# canSlaveV06a.net
KiCad netlist of a schematic drawn in EAGLE
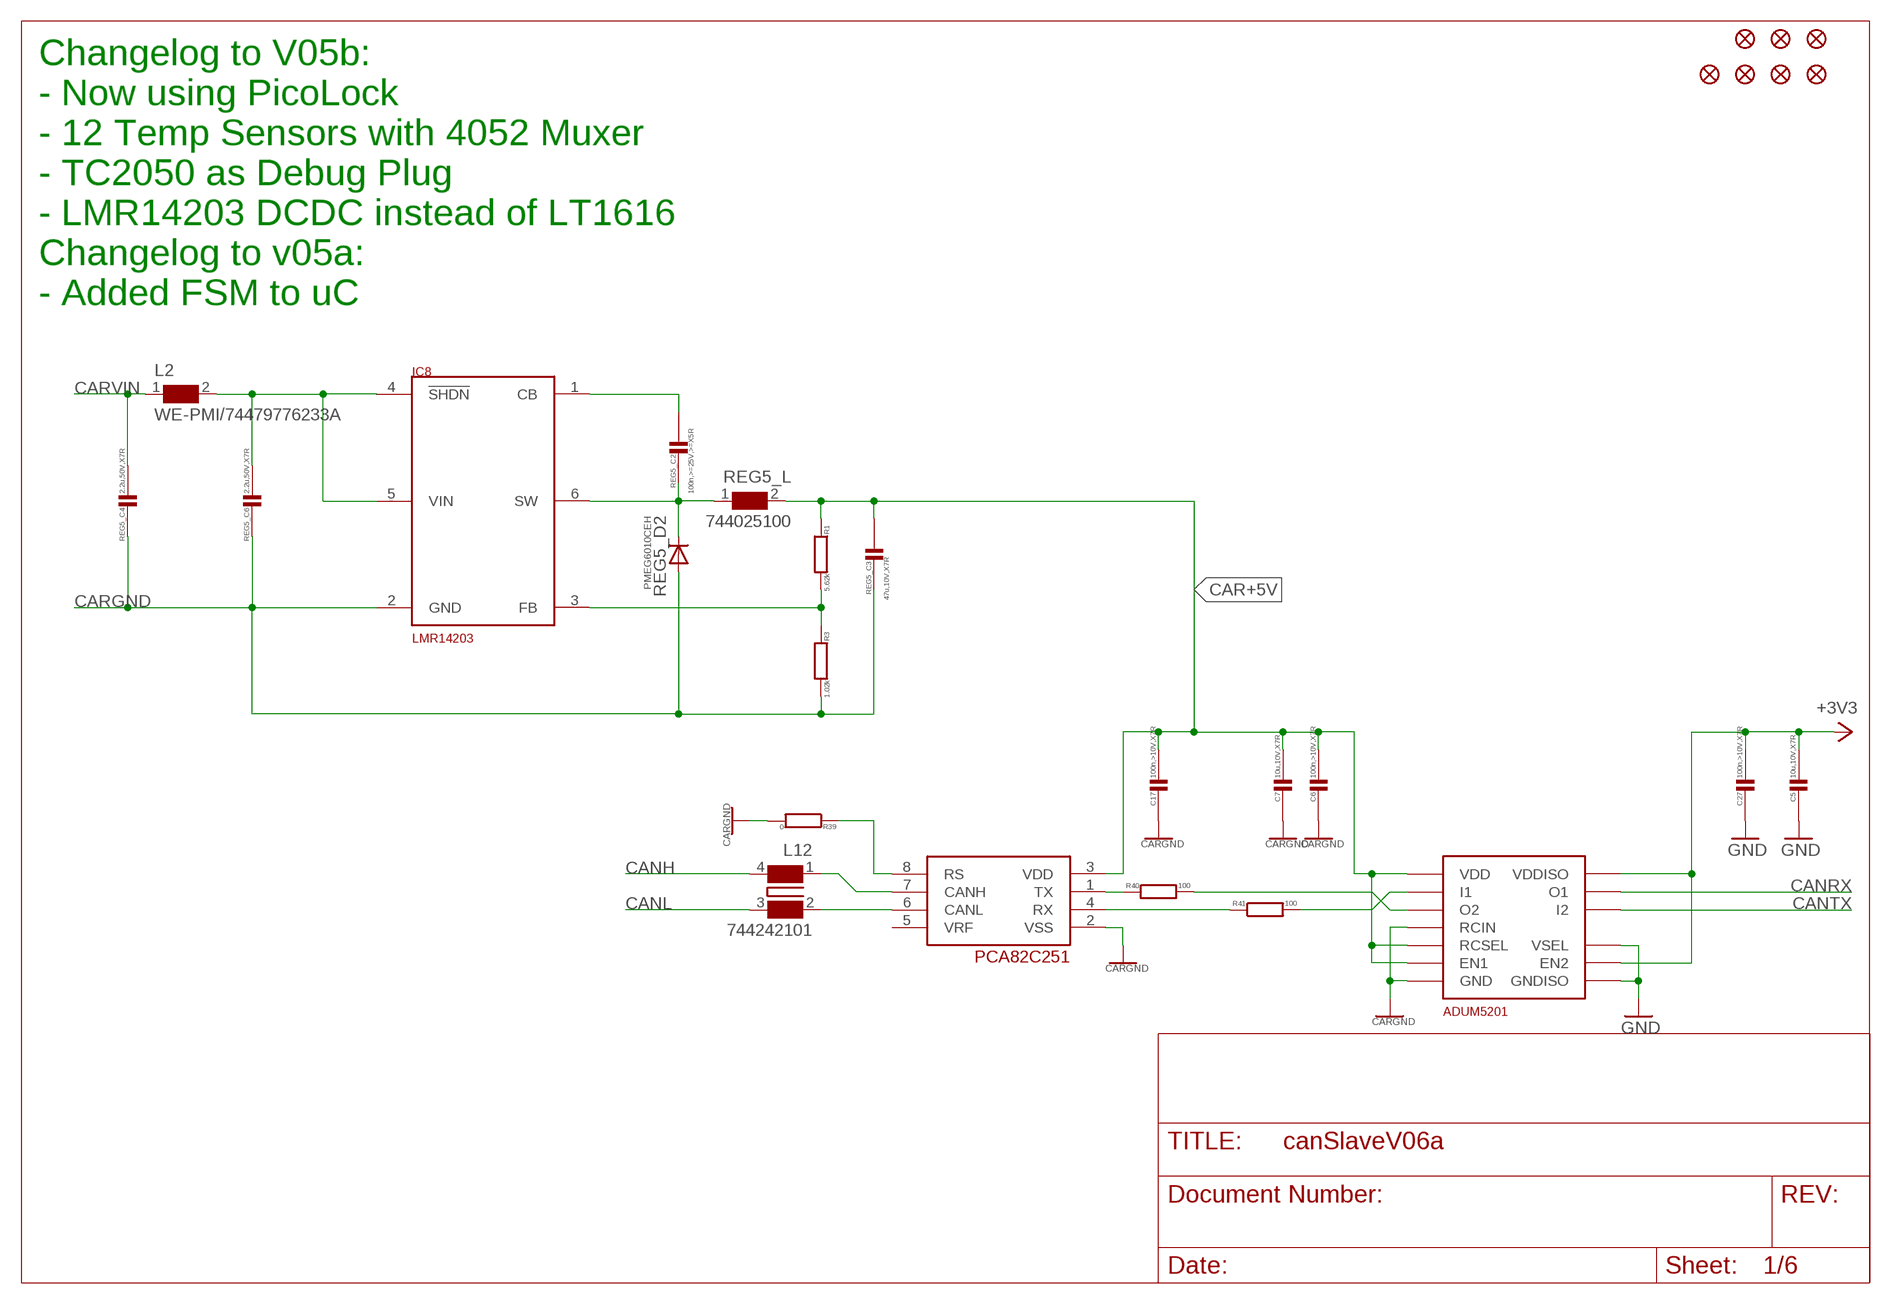
[diagram p0: schematic, sheet 1]
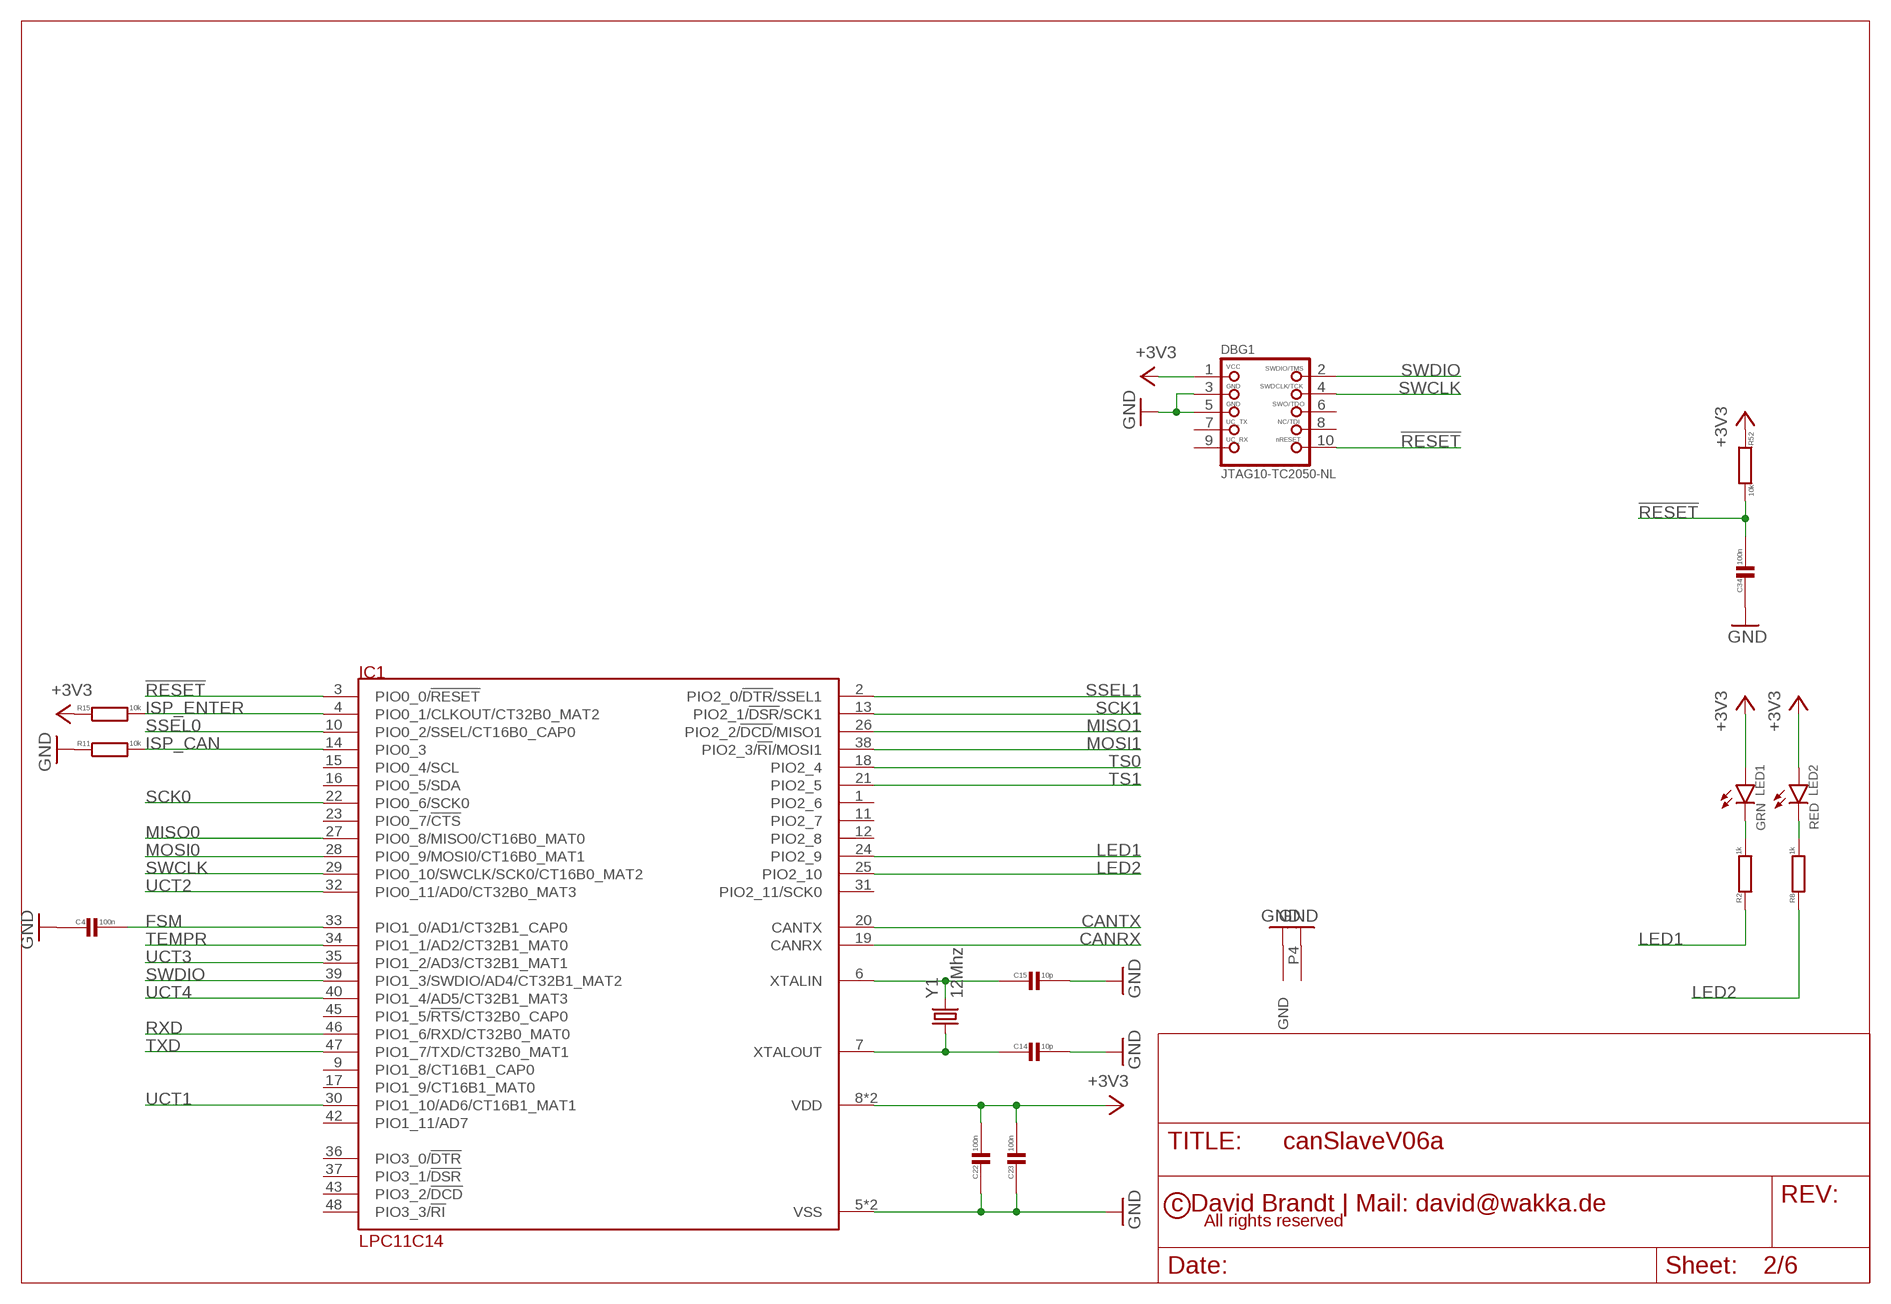
[diagram p1: schematic, sheet 2]
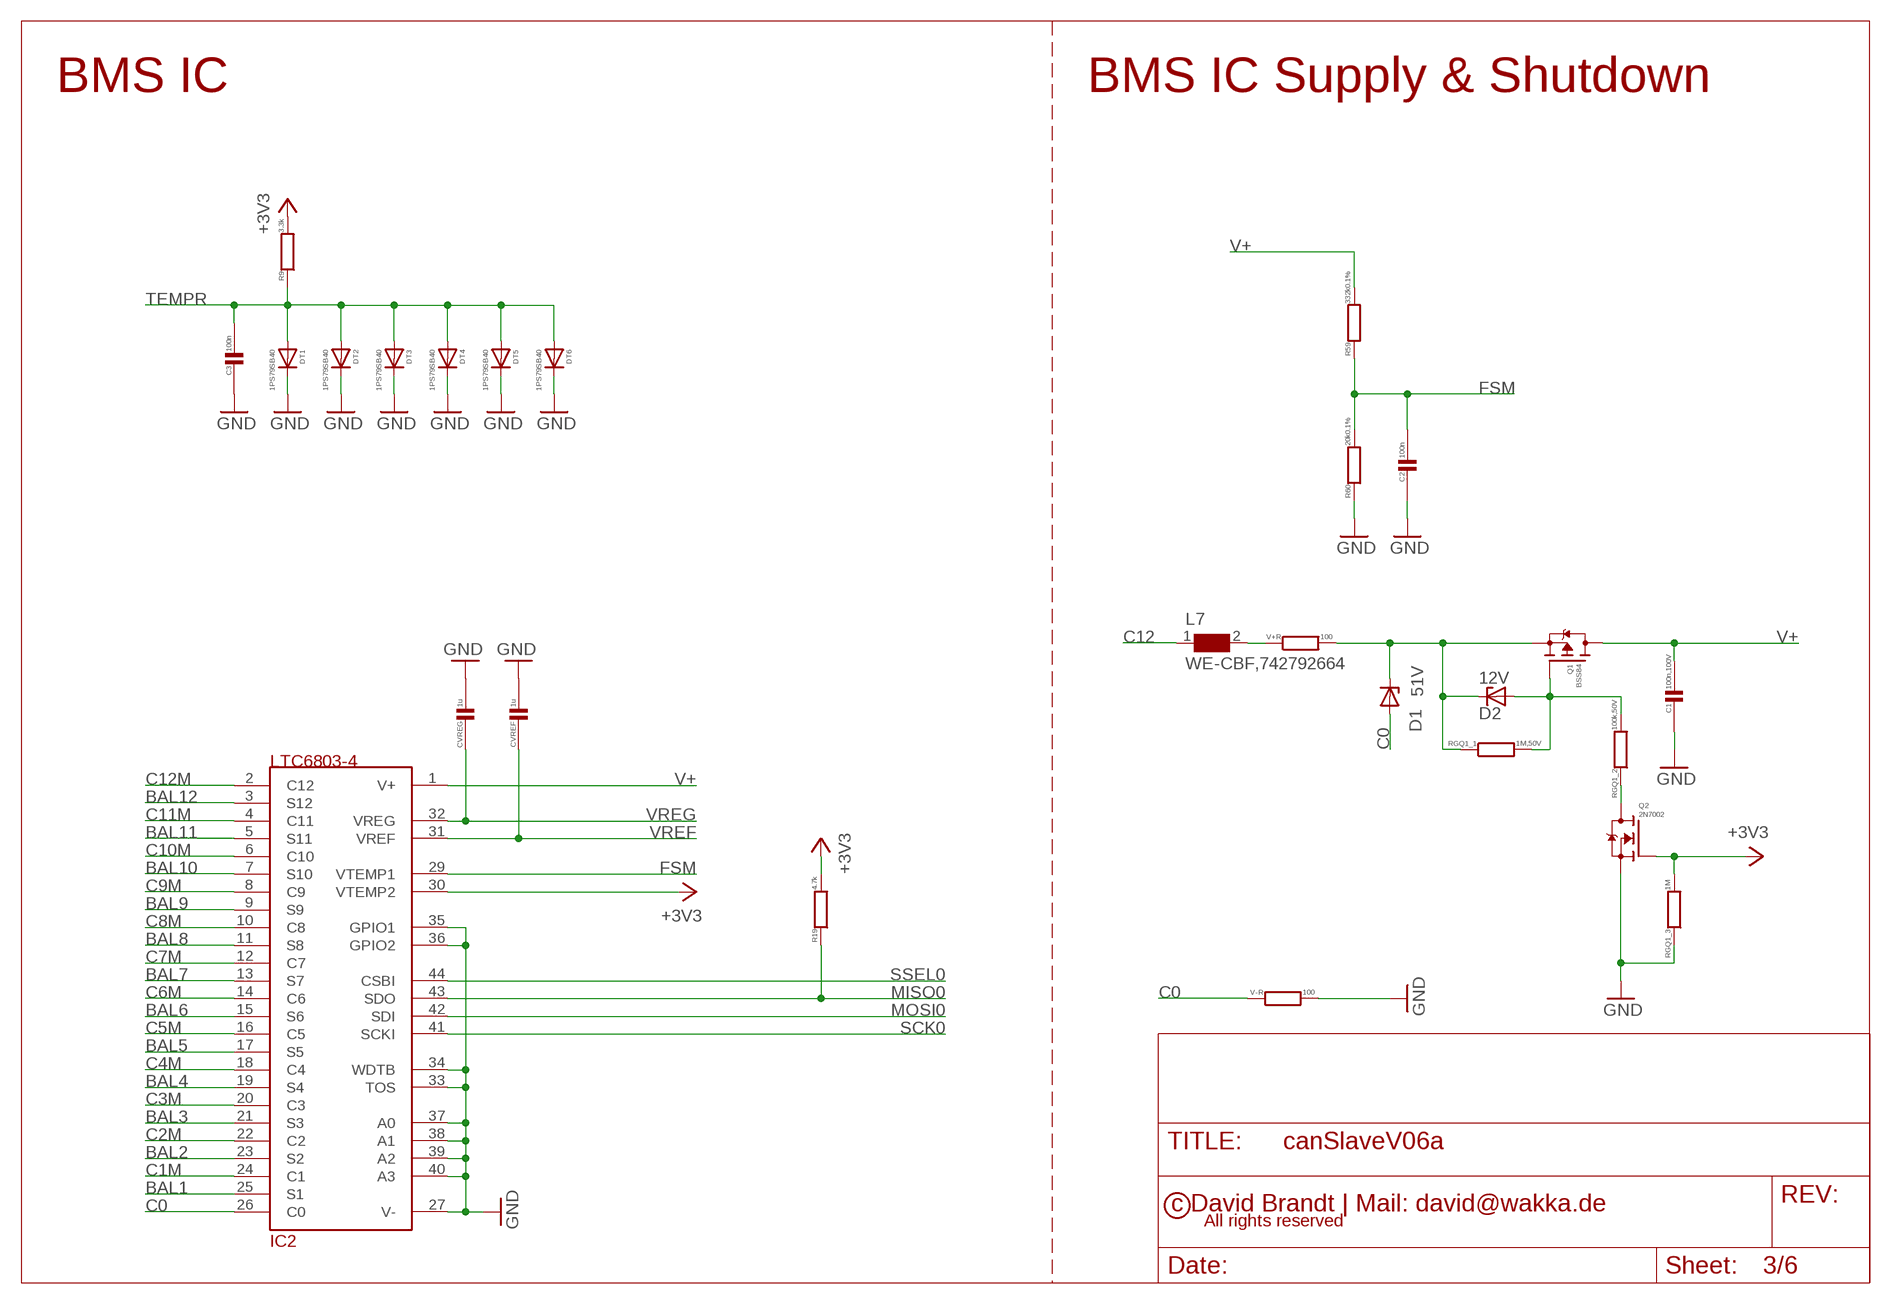
[diagram p2: schematic, sheet 3]
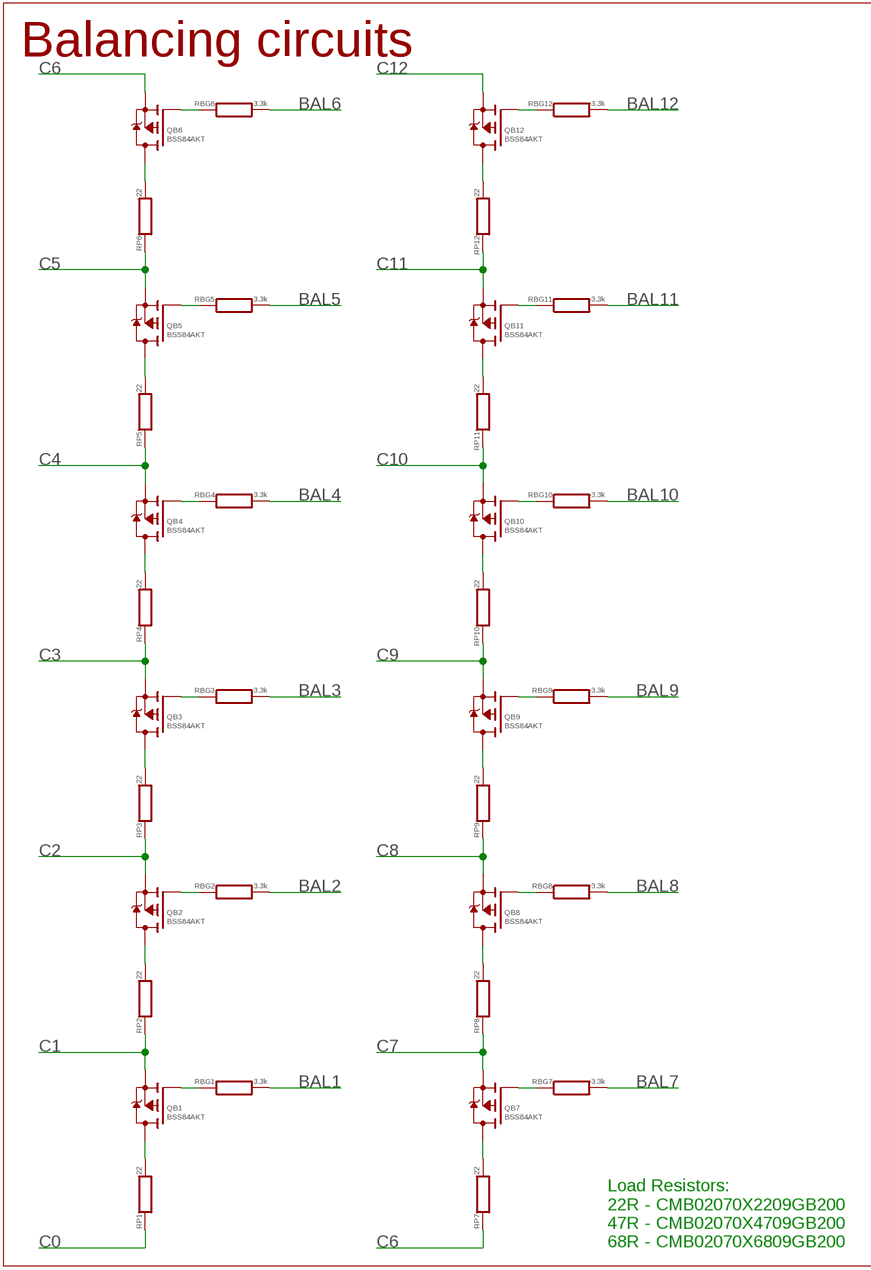
[diagram p3: schematic, sheet 4, part 1 of 2]
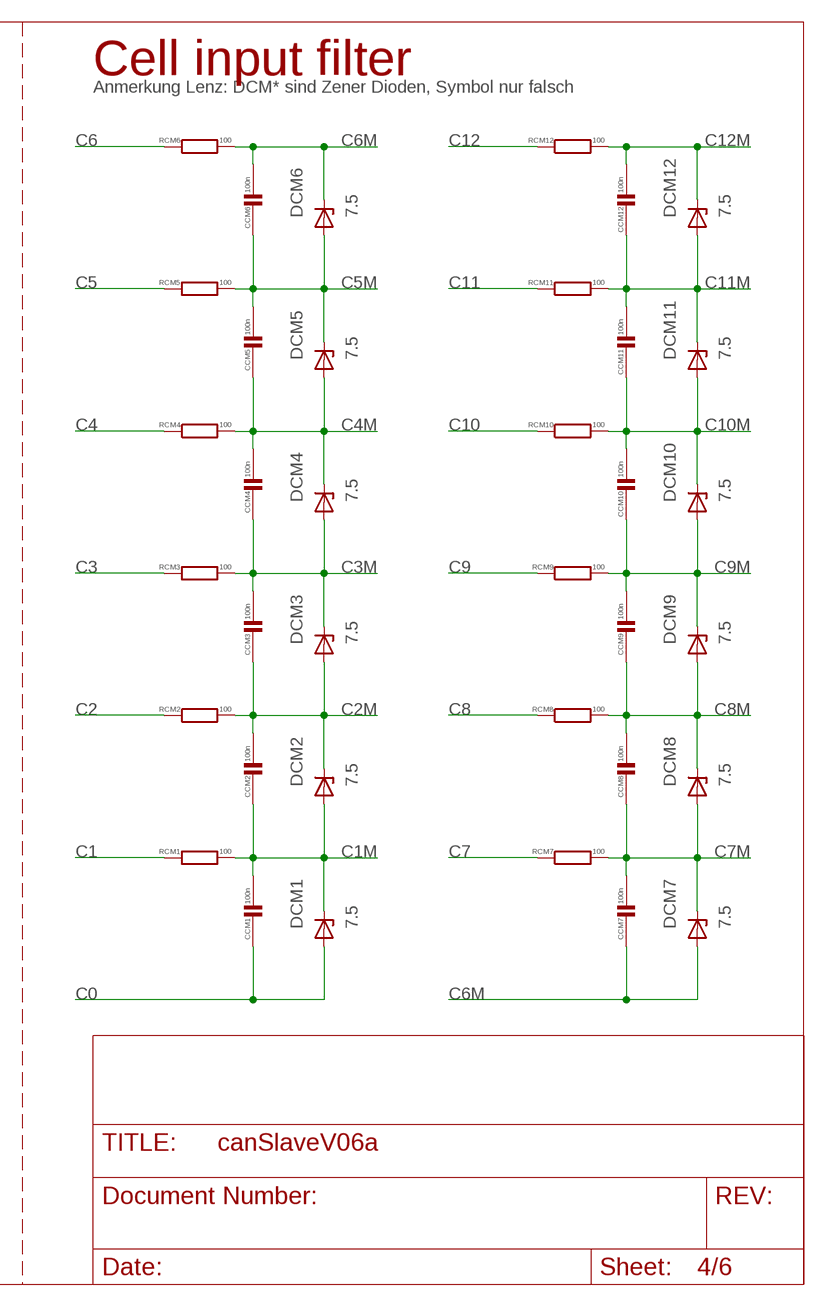
[diagram p4: schematic, sheet 4, part 2 of 2]
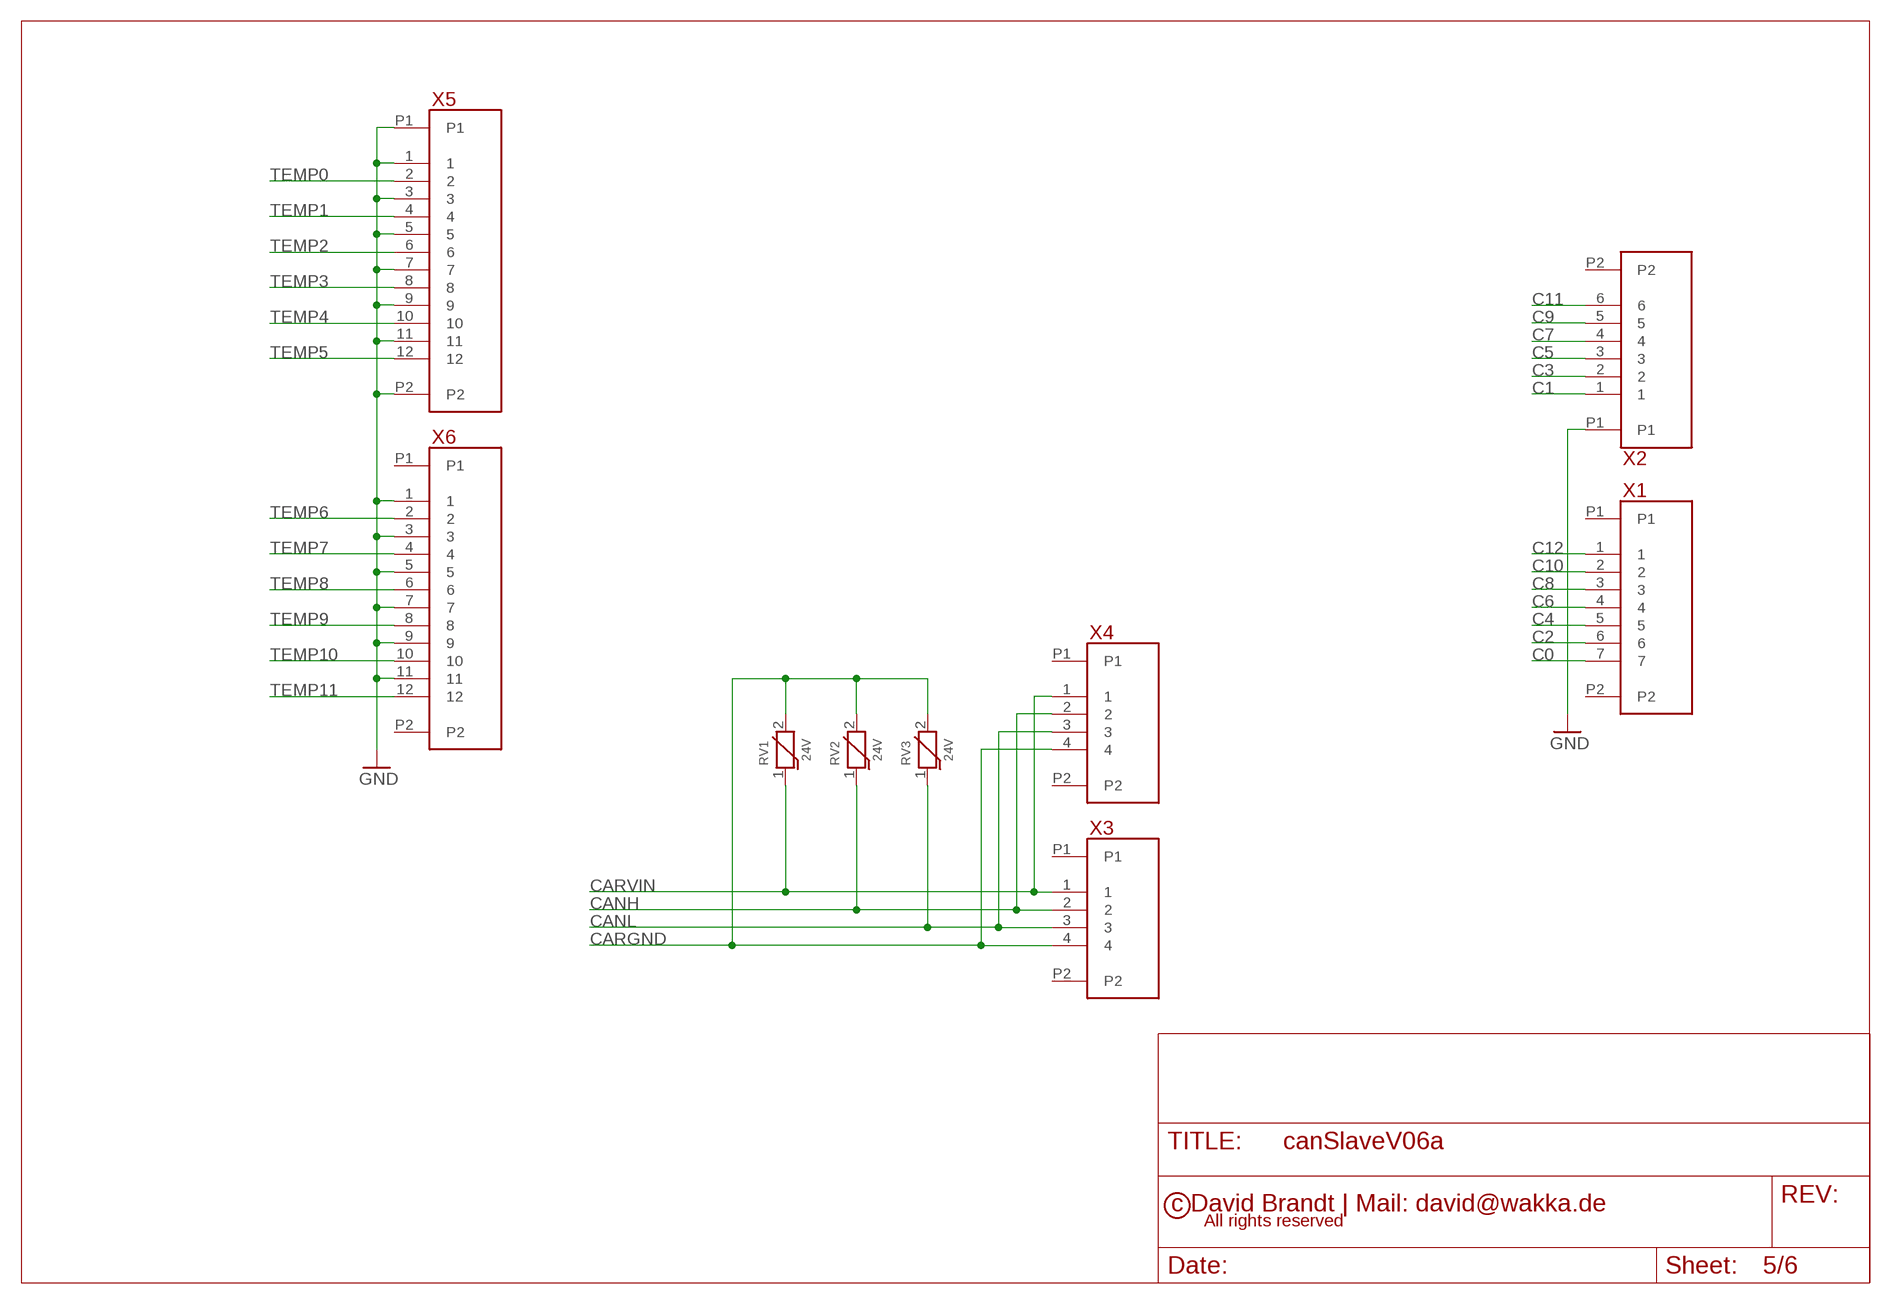
[diagram p5: schematic, sheet 5]
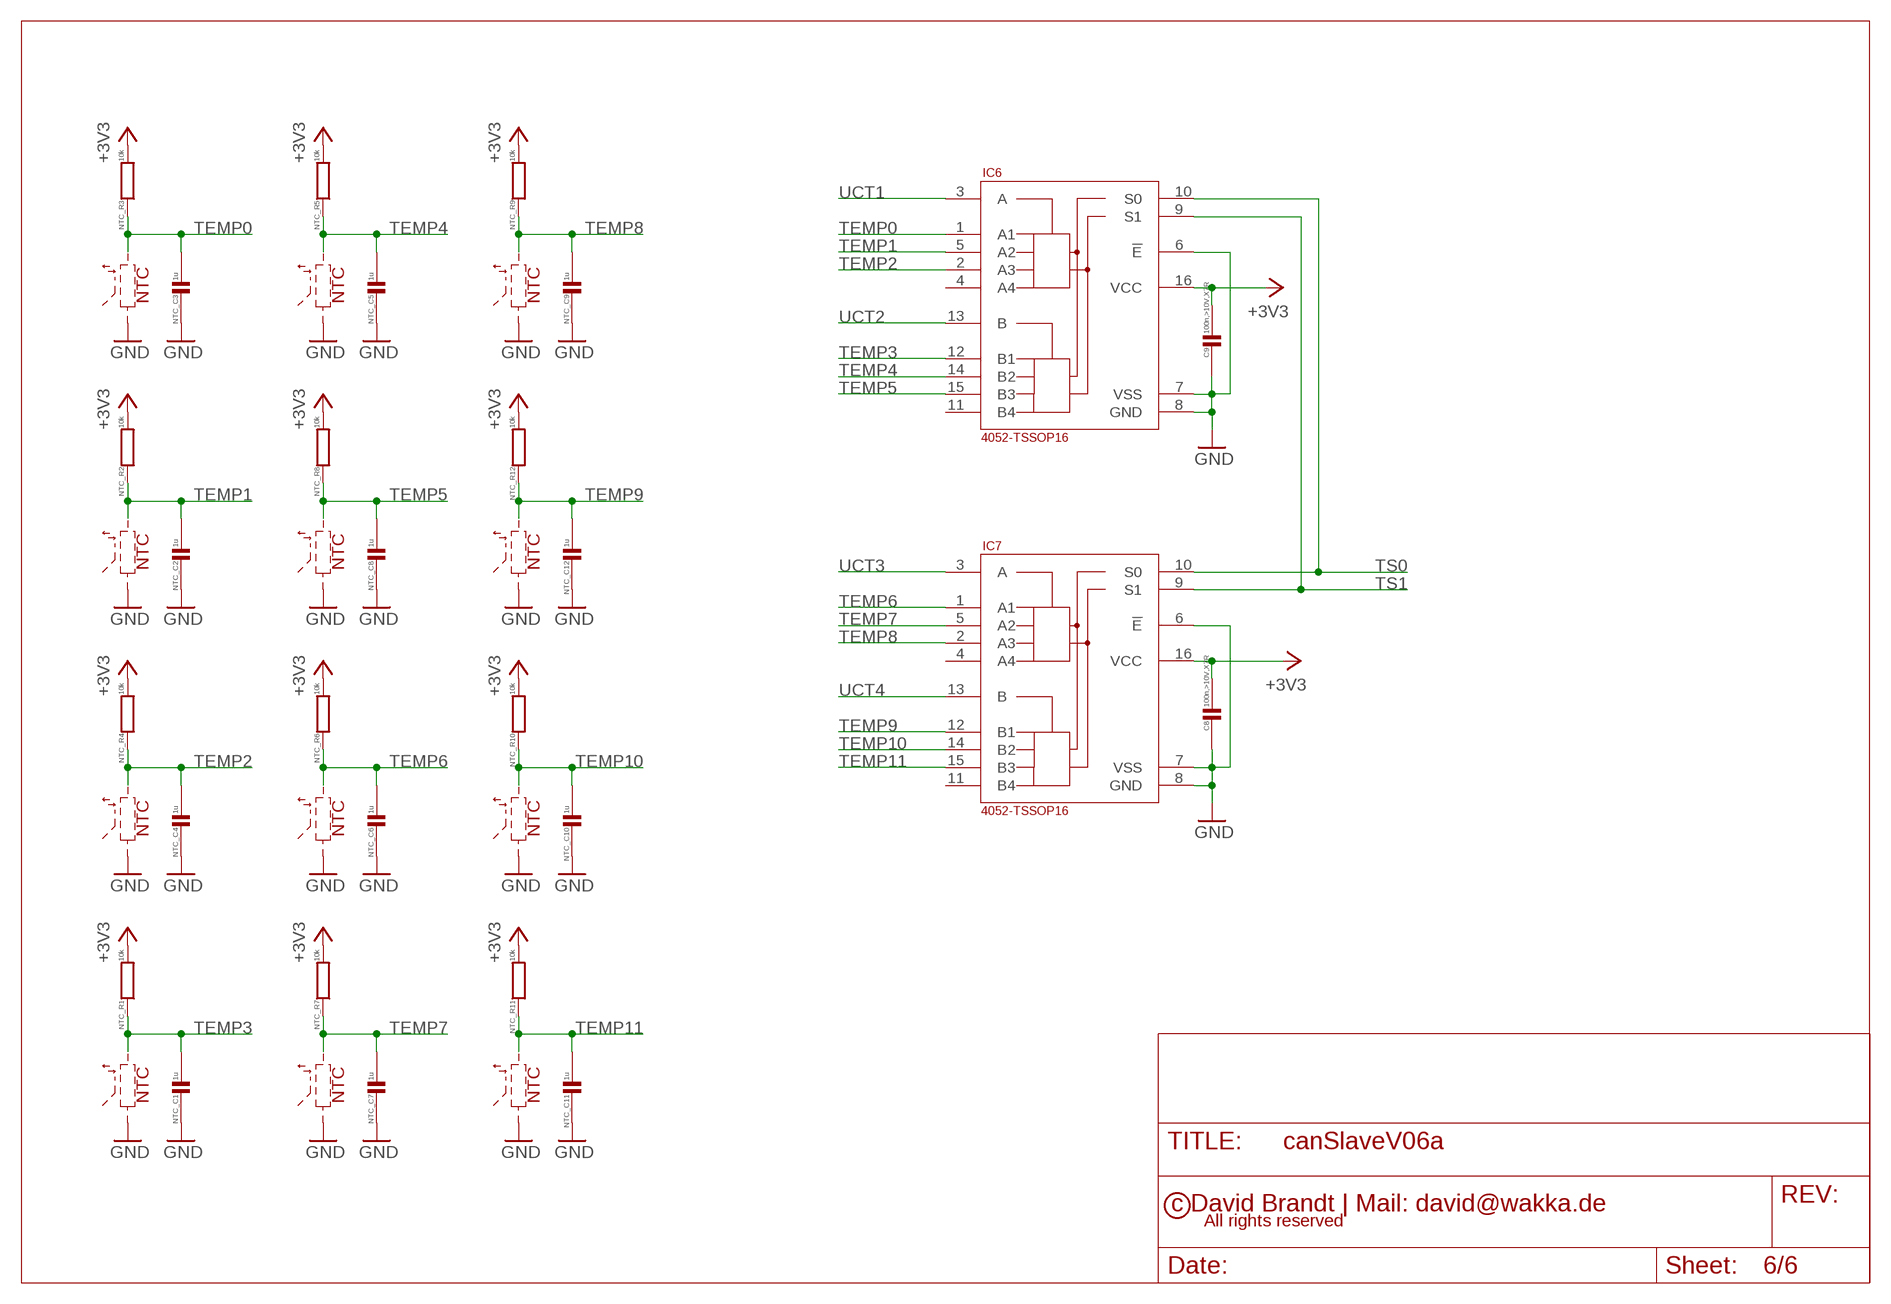
[diagram p6: schematic, sheet 6]

(export (version "E")
  (design (tool "Eeschema 10.0.6"))
  (components
    (comp (ref "CCM1")
      (value "100n")
      (footprint "eagle-import:C0402")
      (libsource (lib "eagle-import") (part "C0402"))
    )
    (comp (ref "CCM2")
      (value "100n")
      (footprint "eagle-import:C0402")
      (libsource (lib "eagle-import") (part "C0402"))
    )
    (comp (ref "CCM3")
      (value "100n")
      (footprint "eagle-import:C0402")
      (libsource (lib "eagle-import") (part "C0402"))
    )
    (comp (ref "CCM4")
      (value "100n")
      (footprint "eagle-import:C0402")
      (libsource (lib "eagle-import") (part "C0402"))
    )
    (comp (ref "CCM5")
      (value "100n")
      (footprint "eagle-import:C0402")
      (libsource (lib "eagle-import") (part "C0402"))
    )
    (comp (ref "CCM6")
      (value "100n")
      (footprint "eagle-import:C0402")
      (libsource (lib "eagle-import") (part "C0402"))
    )
    (comp (ref "CCM7")
      (value "100n")
      (footprint "eagle-import:C0402")
      (libsource (lib "eagle-import") (part "C0402"))
    )
    (comp (ref "CCM8")
      (value "100n")
      (footprint "eagle-import:C0402")
      (libsource (lib "eagle-import") (part "C0402"))
    )
    (comp (ref "CCM9")
      (value "100n")
      (footprint "eagle-import:C0402")
      (libsource (lib "eagle-import") (part "C0402"))
    )
    (comp (ref "CCM10")
      (value "100n")
      (footprint "eagle-import:C0402")
      (libsource (lib "eagle-import") (part "C0402"))
    )
    (comp (ref "CCM11")
      (value "100n")
      (footprint "eagle-import:C0402")
      (libsource (lib "eagle-import") (part "C0402"))
    )
    (comp (ref "CCM12")
      (value "100n")
      (footprint "eagle-import:C0402")
      (libsource (lib "eagle-import") (part "C0402"))
    )
    (comp (ref "DCM1")
      (value "7.5")
      (footprint "eagle-import:SOD523")
      (libsource (lib "eagle-import") (part "ZENERSOD523"))
    )
    (comp (ref "DCM2")
      (value "7.5")
      (footprint "eagle-import:SOD523")
      (libsource (lib "eagle-import") (part "ZENERSOD523"))
    )
    (comp (ref "DCM3")
      (value "7.5")
      (footprint "eagle-import:SOD523")
      (libsource (lib "eagle-import") (part "ZENERSOD523"))
    )
    (comp (ref "DCM4")
      (value "7.5")
      (footprint "eagle-import:SOD523")
      (libsource (lib "eagle-import") (part "ZENERSOD523"))
    )
    (comp (ref "DCM5")
      (value "7.5")
      (footprint "eagle-import:SOD523")
      (libsource (lib "eagle-import") (part "ZENERSOD523"))
    )
    (comp (ref "DCM6")
      (value "7.5")
      (footprint "eagle-import:SOD523")
      (libsource (lib "eagle-import") (part "ZENERSOD523"))
    )
    (comp (ref "DCM7")
      (value "7.5")
      (footprint "eagle-import:SOD523")
      (libsource (lib "eagle-import") (part "ZENERSOD523"))
    )
    (comp (ref "DCM8")
      (value "7.5")
      (footprint "eagle-import:SOD523")
      (libsource (lib "eagle-import") (part "ZENERSOD523"))
    )
    (comp (ref "DCM9")
      (value "7.5")
      (footprint "eagle-import:SOD523")
      (libsource (lib "eagle-import") (part "ZENERSOD523"))
    )
    (comp (ref "DCM10")
      (value "7.5")
      (footprint "eagle-import:SOD523")
      (libsource (lib "eagle-import") (part "ZENERSOD523"))
    )
    (comp (ref "DCM11")
      (value "7.5")
      (footprint "eagle-import:SOD523")
      (libsource (lib "eagle-import") (part "ZENERSOD523"))
    )
    (comp (ref "DCM12")
      (value "7.5")
      (footprint "eagle-import:SOD523")
      (libsource (lib "eagle-import") (part "ZENERSOD523"))
    )
    (comp (ref "QB1")
      (value "BSS84AKT")
      (footprint "eagle-import:SOT416")
      (libsource (lib "eagle-import") (part "BSS84AKT"))
    )
    (comp (ref "QB2")
      (value "BSS84AKT")
      (footprint "eagle-import:SOT416")
      (libsource (lib "eagle-import") (part "BSS84AKT"))
    )
    (comp (ref "QB3")
      (value "BSS84AKT")
      (footprint "eagle-import:SOT416")
      (libsource (lib "eagle-import") (part "BSS84AKT"))
    )
    (comp (ref "QB4")
      (value "BSS84AKT")
      (footprint "eagle-import:SOT416")
      (libsource (lib "eagle-import") (part "BSS84AKT"))
    )
    (comp (ref "QB5")
      (value "BSS84AKT")
      (footprint "eagle-import:SOT416")
      (libsource (lib "eagle-import") (part "BSS84AKT"))
    )
    (comp (ref "QB6")
      (value "BSS84AKT")
      (footprint "eagle-import:SOT416")
      (libsource (lib "eagle-import") (part "BSS84AKT"))
    )
    (comp (ref "QB7")
      (value "BSS84AKT")
      (footprint "eagle-import:SOT416")
      (libsource (lib "eagle-import") (part "BSS84AKT"))
    )
    (comp (ref "QB8")
      (value "BSS84AKT")
      (footprint "eagle-import:SOT416")
      (libsource (lib "eagle-import") (part "BSS84AKT"))
    )
    (comp (ref "QB9")
      (value "BSS84AKT")
      (footprint "eagle-import:SOT416")
      (libsource (lib "eagle-import") (part "BSS84AKT"))
    )
    (comp (ref "QB10")
      (value "BSS84AKT")
      (footprint "eagle-import:SOT416")
      (libsource (lib "eagle-import") (part "BSS84AKT"))
    )
    (comp (ref "QB11")
      (value "BSS84AKT")
      (footprint "eagle-import:SOT416")
      (libsource (lib "eagle-import") (part "BSS84AKT"))
    )
    (comp (ref "QB12")
      (value "BSS84AKT")
      (footprint "eagle-import:SOT416")
      (libsource (lib "eagle-import") (part "BSS84AKT"))
    )
    (comp (ref "RBG1")
      (value "3.3k")
      (footprint "eagle-import:R0402")
      (libsource (lib "eagle-import") (part "R0402"))
    )
    (comp (ref "RBG2")
      (value "3.3k")
      (footprint "eagle-import:R0402")
      (libsource (lib "eagle-import") (part "R0402"))
    )
    (comp (ref "RBG3")
      (value "3.3k")
      (footprint "eagle-import:R0402")
      (libsource (lib "eagle-import") (part "R0402"))
    )
    (comp (ref "RBG4")
      (value "3.3k")
      (footprint "eagle-import:R0402")
      (libsource (lib "eagle-import") (part "R0402"))
    )
    (comp (ref "RBG5")
      (value "3.3k")
      (footprint "eagle-import:R0402")
      (libsource (lib "eagle-import") (part "R0402"))
    )
    (comp (ref "RBG6")
      (value "3.3k")
      (footprint "eagle-import:R0402")
      (libsource (lib "eagle-import") (part "R0402"))
    )
    (comp (ref "RBG7")
      (value "3.3k")
      (footprint "eagle-import:R0402")
      (libsource (lib "eagle-import") (part "R0402"))
    )
    (comp (ref "RBG8")
      (value "3.3k")
      (footprint "eagle-import:R0402")
      (libsource (lib "eagle-import") (part "R0402"))
    )
    (comp (ref "RBG9")
      (value "3.3k")
      (footprint "eagle-import:R0402")
      (libsource (lib "eagle-import") (part "R0402"))
    )
    (comp (ref "RBG10")
      (value "3.3k")
      (footprint "eagle-import:R0402")
      (libsource (lib "eagle-import") (part "R0402"))
    )
    (comp (ref "RBG11")
      (value "3.3k")
      (footprint "eagle-import:R0402")
      (libsource (lib "eagle-import") (part "R0402"))
    )
    (comp (ref "RBG12")
      (value "3.3k")
      (footprint "eagle-import:R0402")
      (libsource (lib "eagle-import") (part "R0402"))
    )
    (comp (ref "RCM1")
      (value "100")
      (footprint "eagle-import:R0402")
      (libsource (lib "eagle-import") (part "R0402"))
    )
    (comp (ref "RCM2")
      (value "100")
      (footprint "eagle-import:R0402")
      (libsource (lib "eagle-import") (part "R0402"))
    )
    (comp (ref "RCM3")
      (value "100")
      (footprint "eagle-import:R0402")
      (libsource (lib "eagle-import") (part "R0402"))
    )
    (comp (ref "RCM4")
      (value "100")
      (footprint "eagle-import:R0402")
      (libsource (lib "eagle-import") (part "R0402"))
    )
    (comp (ref "RCM5")
      (value "100")
      (footprint "eagle-import:R0402")
      (libsource (lib "eagle-import") (part "R0402"))
    )
    (comp (ref "RCM6")
      (value "100")
      (footprint "eagle-import:R0402")
      (libsource (lib "eagle-import") (part "R0402"))
    )
    (comp (ref "RCM7")
      (value "100")
      (footprint "eagle-import:R0402")
      (libsource (lib "eagle-import") (part "R0402"))
    )
    (comp (ref "RCM8")
      (value "100")
      (footprint "eagle-import:R0402")
      (libsource (lib "eagle-import") (part "R0402"))
    )
    (comp (ref "RCM9")
      (value "100")
      (footprint "eagle-import:R0402")
      (libsource (lib "eagle-import") (part "R0402"))
    )
    (comp (ref "RCM10")
      (value "100")
      (footprint "eagle-import:R0402")
      (libsource (lib "eagle-import") (part "R0402"))
    )
    (comp (ref "RCM11")
      (value "100")
      (footprint "eagle-import:R0402")
      (libsource (lib "eagle-import") (part "R0402"))
    )
    (comp (ref "RCM12")
      (value "100")
      (footprint "eagle-import:R0402")
      (libsource (lib "eagle-import") (part "R0402"))
    )
    (comp (ref "RP1")
      (value "22")
      (footprint "eagle-import:MINI_MELF-0207R")
      (libsource (lib "eagle-import") (part "RMELF-0207R"))
    )
    (comp (ref "RP2")
      (value "22")
      (footprint "eagle-import:MINI_MELF-0207R")
      (libsource (lib "eagle-import") (part "RMELF-0207R"))
    )
    (comp (ref "RP3")
      (value "22")
      (footprint "eagle-import:MINI_MELF-0207R")
      (libsource (lib "eagle-import") (part "RMELF-0207R"))
    )
    (comp (ref "RP4")
      (value "22")
      (footprint "eagle-import:MINI_MELF-0207R")
      (libsource (lib "eagle-import") (part "RMELF-0207R"))
    )
    (comp (ref "RP5")
      (value "22")
      (footprint "eagle-import:MINI_MELF-0207R")
      (libsource (lib "eagle-import") (part "RMELF-0207R"))
    )
    (comp (ref "RP6")
      (value "22")
      (footprint "eagle-import:MINI_MELF-0207R")
      (libsource (lib "eagle-import") (part "RMELF-0207R"))
    )
    (comp (ref "RP7")
      (value "22")
      (footprint "eagle-import:MINI_MELF-0207R")
      (libsource (lib "eagle-import") (part "RMELF-0207R"))
    )
    (comp (ref "RP8")
      (value "22")
      (footprint "eagle-import:MINI_MELF-0207R")
      (libsource (lib "eagle-import") (part "RMELF-0207R"))
    )
    (comp (ref "RP9")
      (value "22")
      (footprint "eagle-import:MINI_MELF-0207R")
      (libsource (lib "eagle-import") (part "RMELF-0207R"))
    )
    (comp (ref "RP10")
      (value "22")
      (footprint "eagle-import:MINI_MELF-0207R")
      (libsource (lib "eagle-import") (part "RMELF-0207R"))
    )
    (comp (ref "RP11")
      (value "22")
      (footprint "eagle-import:MINI_MELF-0207R")
      (libsource (lib "eagle-import") (part "RMELF-0207R"))
    )
    (comp (ref "RP12")
      (value "22")
      (footprint "eagle-import:MINI_MELF-0207R")
      (libsource (lib "eagle-import") (part "RMELF-0207R"))
    )
    (comp (ref "C8")
      (value "100n,>10V,X7R")
      (footprint "eagle-import:C0402")
      (libsource (lib "eagle-import") (part "C0402"))
    )
    (comp (ref "C9")
      (value "100n,>10V,X7R")
      (footprint "eagle-import:C0402")
      (libsource (lib "eagle-import") (part "C0402"))
    )
    (comp (ref "IC6")
      (value "4052-TSSOP16")
      (footprint "eagle-import:TSSOP16")
      (libsource (lib "eagle-import") (part "4052-TSSOP16"))
    )
    (comp (ref "IC7")
      (value "4052-TSSOP16")
      (footprint "eagle-import:TSSOP16")
      (libsource (lib "eagle-import") (part "4052-TSSOP16"))
    )
    (comp (ref "NTC_C1")
      (value "1u")
      (footprint "eagle-import:C0402")
      (libsource (lib "eagle-import") (part "C0402"))
    )
    (comp (ref "NTC_C2")
      (value "1u")
      (footprint "eagle-import:C0402")
      (libsource (lib "eagle-import") (part "C0402"))
    )
    (comp (ref "NTC_C3")
      (value "1u")
      (footprint "eagle-import:C0402")
      (libsource (lib "eagle-import") (part "C0402"))
    )
    (comp (ref "NTC_C4")
      (value "1u")
      (footprint "eagle-import:C0402")
      (libsource (lib "eagle-import") (part "C0402"))
    )
    (comp (ref "NTC_C5")
      (value "1u")
      (footprint "eagle-import:C0402")
      (libsource (lib "eagle-import") (part "C0402"))
    )
    (comp (ref "NTC_C6")
      (value "1u")
      (footprint "eagle-import:C0402")
      (libsource (lib "eagle-import") (part "C0402"))
    )
    (comp (ref "NTC_C7")
      (value "1u")
      (footprint "eagle-import:C0402")
      (libsource (lib "eagle-import") (part "C0402"))
    )
    (comp (ref "NTC_C8")
      (value "1u")
      (footprint "eagle-import:C0402")
      (libsource (lib "eagle-import") (part "C0402"))
    )
    (comp (ref "NTC_C9")
      (value "1u")
      (footprint "eagle-import:C0402")
      (libsource (lib "eagle-import") (part "C0402"))
    )
    (comp (ref "NTC_C10")
      (value "1u")
      (footprint "eagle-import:C0402")
      (libsource (lib "eagle-import") (part "C0402"))
    )
    (comp (ref "NTC_C11")
      (value "1u")
      (footprint "eagle-import:C0402")
      (libsource (lib "eagle-import") (part "C0402"))
    )
    (comp (ref "NTC_C12")
      (value "1u")
      (footprint "eagle-import:C0402")
      (libsource (lib "eagle-import") (part "C0402"))
    )
    (comp (ref "NTC_R1")
      (value "10k")
      (footprint "eagle-import:R0402")
      (libsource (lib "eagle-import") (part "R0402"))
    )
    (comp (ref "NTC_R2")
      (value "10k")
      (footprint "eagle-import:R0402")
      (libsource (lib "eagle-import") (part "R0402"))
    )
    (comp (ref "NTC_R3")
      (value "10k")
      (footprint "eagle-import:R0402")
      (libsource (lib "eagle-import") (part "R0402"))
    )
    (comp (ref "NTC_R4")
      (value "10k")
      (footprint "eagle-import:R0402")
      (libsource (lib "eagle-import") (part "R0402"))
    )
    (comp (ref "NTC_R5")
      (value "10k")
      (footprint "eagle-import:R0402")
      (libsource (lib "eagle-import") (part "R0402"))
    )
    (comp (ref "NTC_R6")
      (value "10k")
      (footprint "eagle-import:R0402")
      (libsource (lib "eagle-import") (part "R0402"))
    )
    (comp (ref "NTC_R7")
      (value "10k")
      (footprint "eagle-import:R0402")
      (libsource (lib "eagle-import") (part "R0402"))
    )
    (comp (ref "NTC_R8")
      (value "10k")
      (footprint "eagle-import:R0402")
      (libsource (lib "eagle-import") (part "R0402"))
    )
    (comp (ref "NTC_R9")
      (value "10k")
      (footprint "eagle-import:R0402")
      (libsource (lib "eagle-import") (part "R0402"))
    )
    (comp (ref "NTC_R10")
      (value "10k")
      (footprint "eagle-import:R0402")
      (libsource (lib "eagle-import") (part "R0402"))
    )
    (comp (ref "NTC_R11")
      (value "10k")
      (footprint "eagle-import:R0402")
      (libsource (lib "eagle-import") (part "R0402"))
    )
    (comp (ref "NTC_R12")
      (value "10k")
      (footprint "eagle-import:R0402")
      (libsource (lib "eagle-import") (part "R0402"))
    )
    (comp (ref "RV1")
      (value "24V")
      (footprint "eagle-import:R0603")
      (libsource (lib "eagle-import") (part "VARISTOR0603"))
    )
    (comp (ref "RV2")
      (value "24V")
      (footprint "eagle-import:R0603")
      (libsource (lib "eagle-import") (part "VARISTOR0603"))
    )
    (comp (ref "RV3")
      (value "24V")
      (footprint "eagle-import:R0603")
      (libsource (lib "eagle-import") (part "VARISTOR0603"))
    )
    (comp (ref "X1")
      (value "504050-0791")
      (footprint "eagle-import:504050-0791")
      (libsource (lib "eagle-import") (part "504050-0791"))
    )
    (comp (ref "X2")
      (value "504050-0691")
      (footprint "eagle-import:504050-0691")
      (libsource (lib "eagle-import") (part "504050-0691"))
    )
    (comp (ref "X3")
      (value "504050-0491")
      (footprint "eagle-import:504050-0491")
      (libsource (lib "eagle-import") (part "504050-0491"))
    )
    (comp (ref "X4")
      (value "504050-0491")
      (footprint "eagle-import:504050-0491")
      (libsource (lib "eagle-import") (part "504050-0491"))
    )
    (comp (ref "X5")
      (value "504050-1291")
      (footprint "eagle-import:504050-1291")
      (libsource (lib "eagle-import") (part "504050-1291"))
    )
    (comp (ref "X6")
      (value "504050-1291")
      (footprint "eagle-import:504050-1291")
      (libsource (lib "eagle-import") (part "504050-1291"))
    )
    (comp (ref "C4")
      (value "100n")
      (footprint "eagle-import:C0402")
      (libsource (lib "eagle-import") (part "C0402"))
    )
    (comp (ref "C14")
      (value "10p")
      (footprint "eagle-import:C0402")
      (libsource (lib "eagle-import") (part "C0402"))
    )
    (comp (ref "C15")
      (value "10p")
      (footprint "eagle-import:C0402")
      (libsource (lib "eagle-import") (part "C0402"))
    )
    (comp (ref "C22")
      (value "100n")
      (footprint "eagle-import:C0402")
      (libsource (lib "eagle-import") (part "C0402"))
    )
    (comp (ref "C23")
      (value "100n")
      (footprint "eagle-import:C0402")
      (libsource (lib "eagle-import") (part "C0402"))
    )
    (comp (ref "C34")
      (value "100n")
      (footprint "eagle-import:C0402")
      (libsource (lib "eagle-import") (part "C0402"))
    )
    (comp (ref "DBG1")
      (value "JTAG10-TC2050-NL")
      (footprint "eagle-import:TC2050-NL-JTORDER")
      (libsource (lib "eagle-import") (part "JTAG10-TC2050-NL"))
    )
    (comp (ref "IC1")
      (value "LPC11C14")
      (footprint "eagle-import:LQFP48")
      (libsource (lib "eagle-import") (part "LPC11C1X"))
    )
    (comp (ref "LED1")
      (value "GRN")
      (footprint "eagle-import:CHIPLED_0603")
      (libsource (lib "eagle-import") (part "LED0603"))
    )
    (comp (ref "LED2")
      (value "RED")
      (footprint "eagle-import:CHIPLED_0603")
      (libsource (lib "eagle-import") (part "LED0603"))
    )
    (comp (ref "R2")
      (value "1k")
      (footprint "eagle-import:R0402")
      (libsource (lib "eagle-import") (part "R0402"))
    )
    (comp (ref "R8")
      (value "1k")
      (footprint "eagle-import:R0402")
      (libsource (lib "eagle-import") (part "R0402"))
    )
    (comp (ref "R11")
      (value "10k")
      (footprint "eagle-import:R0402")
      (libsource (lib "eagle-import") (part "R0402"))
    )
    (comp (ref "R15")
      (value "10k")
      (footprint "eagle-import:R0402")
      (libsource (lib "eagle-import") (part "R0402"))
    )
    (comp (ref "R52")
      (value "10k")
      (footprint "eagle-import:R0402")
      (libsource (lib "eagle-import") (part "R0402"))
    )
    (comp (ref "Y1")
      (value "12Mhz")
      (footprint "eagle-import:MT")
      (libsource (lib "eagle-import") (part "CRYSTAL43.2X2.5"))
    )
    (comp (ref "C5")
      (value "10u,10V,X7R")
      (footprint "eagle-import:C0603")
      (libsource (lib "eagle-import") (part "C0603"))
    )
    (comp (ref "C6")
      (value "100n,>10V,X7R")
      (footprint "eagle-import:C0402")
      (libsource (lib "eagle-import") (part "C0402"))
    )
    (comp (ref "C7")
      (value "10u,10V,X7R")
      (footprint "eagle-import:C0603")
      (libsource (lib "eagle-import") (part "C0603"))
    )
    (comp (ref "C17")
      (value "100n,>10V,X7R")
      (footprint "eagle-import:C0402")
      (libsource (lib "eagle-import") (part "C0402"))
    )
    (comp (ref "C27")
      (value "100n,>10V,X7R")
      (footprint "eagle-import:C0402")
      (libsource (lib "eagle-import") (part "C0402"))
    )
    (comp (ref "FID2")
      (value "FIDUCIAL\"\"")
      (footprint "eagle-import:FIDUCIAL_1MM")
      (libsource (lib "eagle-import") (part "FIDUCIAL{dblquote}{dblquote}"))
    )
    (comp (ref "FID3")
      (value "FIDUCIAL\"\"")
      (footprint "eagle-import:FIDUCIAL_1MM")
      (libsource (lib "eagle-import") (part "FIDUCIAL{dblquote}{dblquote}"))
    )
    (comp (ref "FID4")
      (value "FIDUCIAL\"\"")
      (footprint "eagle-import:FIDUCIAL_1MM")
      (libsource (lib "eagle-import") (part "FIDUCIAL{dblquote}{dblquote}"))
    )
    (comp (ref "FID7")
      (value "FIDUCIAL\"\"")
      (footprint "eagle-import:FIDUCIAL_1MM")
      (libsource (lib "eagle-import") (part "FIDUCIAL{dblquote}{dblquote}"))
    )
    (comp (ref "FID8")
      (value "FIDUCIAL\"\"")
      (footprint "eagle-import:FIDUCIAL_1MM")
      (libsource (lib "eagle-import") (part "FIDUCIAL{dblquote}{dblquote}"))
    )
    (comp (ref "FID9")
      (value "FIDUCIAL\"\"")
      (footprint "eagle-import:FIDUCIAL_1MM")
      (libsource (lib "eagle-import") (part "FIDUCIAL{dblquote}{dblquote}"))
    )
    (comp (ref "FID10")
      (value "FIDUCIAL\"\"")
      (footprint "eagle-import:FIDUCIAL_1MM")
      (libsource (lib "eagle-import") (part "FIDUCIAL{dblquote}{dblquote}"))
    )
    (comp (ref "IC4")
      (value "PCA82C251")
      (footprint "eagle-import:SO-8")
      (libsource (lib "eagle-import") (part "MCP2551"))
    )
    (comp (ref "IC5")
      (value "ADUM5201")
      (footprint "eagle-import:SO16WB")
      (libsource (lib "eagle-import") (part "ADUM5201"))
    )
    (comp (ref "IC8")
      (value "LMR14203")
      (footprint "eagle-import:SOT23-6")
      (libsource (lib "eagle-import") (part "LMR1420X"))
    )
    (comp (ref "L2")
      (value "WE-PMI/74479776233A")
      (footprint "eagle-import:WE-PMI_0806")
      (libsource (lib "eagle-import") (part "WE-PMI_0806"))
    )
    (comp (ref "L12")
      (value "744242101")
      (footprint "eagle-import:WE-SLM")
      (libsource (lib "eagle-import") (part "WE-SLM"))
    )
    (comp (ref "R1")
      (value "5.62k")
      (footprint "eagle-import:R0402")
      (libsource (lib "eagle-import") (part "R0402"))
    )
    (comp (ref "R3")
      (value "1.02k")
      (footprint "eagle-import:R0402")
      (libsource (lib "eagle-import") (part "R0402"))
    )
    (comp (ref "R39")
      (value "0")
      (footprint "eagle-import:R0402")
      (libsource (lib "eagle-import") (part "R0402"))
    )
    (comp (ref "R40")
      (value "100")
      (footprint "eagle-import:R0402")
      (libsource (lib "eagle-import") (part "R0402"))
    )
    (comp (ref "R41")
      (value "100")
      (footprint "eagle-import:R0402")
      (libsource (lib "eagle-import") (part "R0402"))
    )
    (comp (ref "REG5_C2")
      (value "100n,>=25V,>=X5R")
      (footprint "eagle-import:C0402")
      (libsource (lib "eagle-import") (part "C0402"))
    )
    (comp (ref "REG5_C3")
      (value "47u,10V,X7R")
      (footprint "eagle-import:C1210")
      (libsource (lib "eagle-import") (part "C1210"))
    )
    (comp (ref "REG5_C4")
      (value "2.2u,50V,X7R")
      (footprint "eagle-import:C0805")
      (libsource (lib "eagle-import") (part "C0805"))
    )
    (comp (ref "REG5_C6")
      (value "2.2u,50V,X7R")
      (footprint "eagle-import:C0805")
      (libsource (lib "eagle-import") (part "C0805"))
    )
    (comp (ref "REG5_D2")
      (value "PMEG6010CEH")
      (footprint "eagle-import:SOD123")
      (libsource (lib "eagle-import") (part "D-SOD123"))
    )
    (comp (ref "REG5_L")
      (value "744025100")
      (footprint "eagle-import:WE-TPC_2828")
      (libsource (lib "eagle-import") (part "WE-TPC_2828"))
    )
    (comp (ref "C1")
      (value "100n,100V")
      (footprint "eagle-import:C0603")
      (libsource (lib "eagle-import") (part "C0603"))
    )
    (comp (ref "C2")
      (value "100n")
      (footprint "eagle-import:C0402")
      (libsource (lib "eagle-import") (part "C0402"))
    )
    (comp (ref "C3")
      (value "100n")
      (footprint "eagle-import:C0402")
      (libsource (lib "eagle-import") (part "C0402"))
    )
    (comp (ref "CVREF")
      (value "1u")
      (footprint "eagle-import:C0402")
      (libsource (lib "eagle-import") (part "C0402"))
    )
    (comp (ref "CVREG")
      (value "1u")
      (footprint "eagle-import:C0402")
      (libsource (lib "eagle-import") (part "C0402"))
    )
    (comp (ref "D1")
      (value "51V")
      (footprint "eagle-import:SOD323-L")
      (libsource (lib "eagle-import") (part "ZENERSOD323"))
    )
    (comp (ref "D2")
      (value "12V")
      (footprint "eagle-import:SOD323-L")
      (libsource (lib "eagle-import") (part "ZENERSOD323"))
    )
    (comp (ref "DT1")
      (value "1PS79SB40")
      (footprint "eagle-import:SOD523")
      (libsource (lib "eagle-import") (part "DIODE-SOD523"))
    )
    (comp (ref "DT2")
      (value "1PS79SB40")
      (footprint "eagle-import:SOD523")
      (libsource (lib "eagle-import") (part "DIODE-SOD523"))
    )
    (comp (ref "DT3")
      (value "1PS79SB40")
      (footprint "eagle-import:SOD523")
      (libsource (lib "eagle-import") (part "DIODE-SOD523"))
    )
    (comp (ref "DT4")
      (value "1PS79SB40")
      (footprint "eagle-import:SOD523")
      (libsource (lib "eagle-import") (part "DIODE-SOD523"))
    )
    (comp (ref "DT5")
      (value "1PS79SB40")
      (footprint "eagle-import:SOD523")
      (libsource (lib "eagle-import") (part "DIODE-SOD523"))
    )
    (comp (ref "DT6")
      (value "1PS79SB40")
      (footprint "eagle-import:SOD523")
      (libsource (lib "eagle-import") (part "DIODE-SOD523"))
    )
    (comp (ref "IC2")
      (value "LTC6803-4")
      (footprint "eagle-import:44SSOP")
      (libsource (lib "eagle-import") (part "LTC6803-4"))
    )
    (comp (ref "L7")
      (value "WE-CBF,742792664")
      (footprint "eagle-import:0603")
      (libsource (lib "eagle-import") (part "WE-CBF_0603"))
    )
    (comp (ref "Q1")
      (value "BSS84")
      (footprint "eagle-import:SOT23")
      (libsource (lib "eagle-import") (part "BSS84"))
    )
    (comp (ref "Q2")
      (value "2N7002")
      (footprint "eagle-import:SOT23")
      (libsource (lib "eagle-import") (part "2N7002"))
    )
    (comp (ref "R9")
      (value "3.3k")
      (footprint "eagle-import:R0603")
      (libsource (lib "eagle-import") (part "R0603"))
    )
    (comp (ref "R19")
      (value "4.7k")
      (footprint "eagle-import:R0402")
      (libsource (lib "eagle-import") (part "R0402"))
    )
    (comp (ref "R59")
      (value "332k0.1%")
      (footprint "eagle-import:R0603")
      (libsource (lib "eagle-import") (part "R0603"))
    )
    (comp (ref "R60")
      (value "20k0.1%")
      (footprint "eagle-import:R0402")
      (libsource (lib "eagle-import") (part "R0402"))
    )
    (comp (ref "RGQ1_1")
      (value "1M,50V")
      (footprint "eagle-import:R0603")
      (libsource (lib "eagle-import") (part "R0603"))
    )
    (comp (ref "RGQ1_2")
      (value "100k,50V")
      (footprint "eagle-import:R0603")
      (libsource (lib "eagle-import") (part "R0603"))
    )
    (comp (ref "RGQ1_3")
      (value "1M")
      (footprint "eagle-import:R0402")
      (libsource (lib "eagle-import") (part "R0402"))
    )
    (comp (ref "V+R")
      (value "100")
      (footprint "eagle-import:R0603")
      (libsource (lib "eagle-import") (part "R0603"))
    )
    (comp (ref "V-R")
      (value "100")
      (footprint "eagle-import:R0603")
      (libsource (lib "eagle-import") (part "R0603"))
    )
  )
  (nets
    (net (code "1") (name "+3V3") (class "Default")
      (node (ref "C22") (pin "1") (pinfunction "1_1") (pintype "passive"))
      (node (ref "C23") (pin "1") (pinfunction "1_1") (pintype "passive"))
      (node (ref "C27") (pin "1") (pinfunction "1_1") (pintype "passive"))
      (node (ref "C5") (pin "1") (pinfunction "1_1") (pintype "passive"))
      (node (ref "C8") (pin "1") (pinfunction "1_1") (pintype "passive"))
      (node (ref "C9") (pin "1") (pinfunction "1_1") (pintype "passive"))
      (node (ref "DBG1") (pin "1") (pinfunction "1_1") (pintype "passive"))
      (node (ref "IC1") (pin "44") (pinfunction "VDD_44") (pintype "bidirectional"))
      (node (ref "IC1") (pin "8") (pinfunction "VDD_8") (pintype "bidirectional"))
      (node (ref "IC2") (pin "30") (pinfunction "VTEMP2_30") (pintype "bidirectional"))
      (node (ref "IC5") (pin "P$10") (pinfunction "EN2_P$10") (pintype "bidirectional"))
      (node (ref "IC5") (pin "P$16") (pinfunction "VDDISO_P$16") (pintype "bidirectional"))
      (node (ref "IC6") (pin "16") (pinfunction "VCC_16") (pintype "bidirectional"))
      (node (ref "IC7") (pin "16") (pinfunction "VCC_16") (pintype "bidirectional"))
      (node (ref "LED1") (pin "A") (pinfunction "A_A") (pintype "passive"))
      (node (ref "LED2") (pin "A") (pinfunction "A_A") (pintype "passive"))
      (node (ref "NTC_R1") (pin "2") (pinfunction "2_2") (pintype "passive"))
      (node (ref "NTC_R10") (pin "2") (pinfunction "2_2") (pintype "passive"))
      (node (ref "NTC_R11") (pin "2") (pinfunction "2_2") (pintype "passive"))
      (node (ref "NTC_R12") (pin "2") (pinfunction "2_2") (pintype "passive"))
      (node (ref "NTC_R2") (pin "2") (pinfunction "2_2") (pintype "passive"))
      (node (ref "NTC_R3") (pin "2") (pinfunction "2_2") (pintype "passive"))
      (node (ref "NTC_R4") (pin "2") (pinfunction "2_2") (pintype "passive"))
      (node (ref "NTC_R5") (pin "2") (pinfunction "2_2") (pintype "passive"))
      (node (ref "NTC_R6") (pin "2") (pinfunction "2_2") (pintype "passive"))
      (node (ref "NTC_R7") (pin "2") (pinfunction "2_2") (pintype "passive"))
      (node (ref "NTC_R8") (pin "2") (pinfunction "2_2") (pintype "passive"))
      (node (ref "NTC_R9") (pin "2") (pinfunction "2_2") (pintype "passive"))
      (node (ref "Q2") (pin "1") (pinfunction "G_1") (pintype "passive"))
      (node (ref "R15") (pin "1") (pinfunction "1_1") (pintype "passive"))
      (node (ref "R19") (pin "2") (pinfunction "2_2") (pintype "passive"))
      (node (ref "R52") (pin "1") (pinfunction "1_1") (pintype "passive"))
      (node (ref "R9") (pin "2") (pinfunction "2_2") (pintype "passive"))
      (node (ref "RGQ1_3") (pin "2") (pinfunction "2_2") (pintype "passive"))
    )
    (net (code "2") (name "BAL1") (class "Default")
      (node (ref "IC2") (pin "25") (pinfunction "S1_25") (pintype "bidirectional"))
      (node (ref "RBG1") (pin "2") (pinfunction "2_2") (pintype "passive"))
    )
    (net (code "3") (name "BAL2") (class "Default")
      (node (ref "IC2") (pin "23") (pinfunction "S2_23") (pintype "bidirectional"))
      (node (ref "RBG2") (pin "2") (pinfunction "2_2") (pintype "passive"))
    )
    (net (code "4") (name "BAL3") (class "Default")
      (node (ref "IC2") (pin "21") (pinfunction "S3_21") (pintype "bidirectional"))
      (node (ref "RBG3") (pin "2") (pinfunction "2_2") (pintype "passive"))
    )
    (net (code "5") (name "BAL4") (class "Default")
      (node (ref "IC2") (pin "19") (pinfunction "S4_19") (pintype "bidirectional"))
      (node (ref "RBG4") (pin "2") (pinfunction "2_2") (pintype "passive"))
    )
    (net (code "6") (name "BAL5") (class "Default")
      (node (ref "IC2") (pin "17") (pinfunction "S5_17") (pintype "bidirectional"))
      (node (ref "RBG5") (pin "2") (pinfunction "2_2") (pintype "passive"))
    )
    (net (code "7") (name "BAL6") (class "Default")
      (node (ref "IC2") (pin "15") (pinfunction "S6_15") (pintype "bidirectional"))
      (node (ref "RBG6") (pin "2") (pinfunction "2_2") (pintype "passive"))
    )
    (net (code "8") (name "BAL7") (class "Default")
      (node (ref "IC2") (pin "13") (pinfunction "S7_13") (pintype "bidirectional"))
      (node (ref "RBG7") (pin "2") (pinfunction "2_2") (pintype "passive"))
    )
    (net (code "9") (name "BAL8") (class "Default")
      (node (ref "IC2") (pin "11") (pinfunction "S8_11") (pintype "bidirectional"))
      (node (ref "RBG8") (pin "2") (pinfunction "2_2") (pintype "passive"))
    )
    (net (code "10") (name "BAL9") (class "Default")
      (node (ref "IC2") (pin "9") (pinfunction "S9_9") (pintype "bidirectional"))
      (node (ref "RBG9") (pin "2") (pinfunction "2_2") (pintype "passive"))
    )
    (net (code "11") (name "BAL10") (class "Default")
      (node (ref "IC2") (pin "7") (pinfunction "S10_7") (pintype "bidirectional"))
      (node (ref "RBG10") (pin "2") (pinfunction "2_2") (pintype "passive"))
    )
    (net (code "12") (name "BAL11") (class "Default")
      (node (ref "IC2") (pin "5") (pinfunction "S11_5") (pintype "bidirectional"))
      (node (ref "RBG11") (pin "2") (pinfunction "2_2") (pintype "passive"))
    )
    (net (code "13") (name "BAL12") (class "Default")
      (node (ref "IC2") (pin "3") (pinfunction "S12_3") (pintype "bidirectional"))
      (node (ref "RBG12") (pin "2") (pinfunction "2_2") (pintype "passive"))
    )
    (net (code "14") (name "C0") (class "Default")
      (node (ref "CCM1") (pin "2") (pinfunction "2_2") (pintype "passive"))
      (node (ref "D1") (pin "A") (pinfunction "A_A") (pintype "passive"))
      (node (ref "DCM1") (pin "A") (pinfunction "A_A") (pintype "passive"))
      (node (ref "IC2") (pin "26") (pinfunction "C0_26") (pintype "bidirectional"))
      (node (ref "RP1") (pin "1") (pinfunction "1_1") (pintype "passive"))
      (node (ref "V-R") (pin "1") (pinfunction "1_1") (pintype "passive"))
      (node (ref "X1") (pin "7") (pinfunction "7_7") (pintype "bidirectional"))
    )
    (net (code "15") (name "C1") (class "Default")
      (node (ref "QB1") (pin "2") (pinfunction "S_2") (pintype "passive"))
      (node (ref "RCM1") (pin "1") (pinfunction "1_1") (pintype "passive"))
      (node (ref "RP2") (pin "1") (pinfunction "1_1") (pintype "passive"))
      (node (ref "X2") (pin "1") (pinfunction "1_1") (pintype "bidirectional"))
    )
    (net (code "16") (name "C1M") (class "Default")
      (node (ref "CCM1") (pin "1") (pinfunction "1_1") (pintype "passive"))
      (node (ref "CCM2") (pin "2") (pinfunction "2_2") (pintype "passive"))
      (node (ref "DCM1") (pin "C") (pinfunction "C_C") (pintype "passive"))
      (node (ref "DCM2") (pin "A") (pinfunction "A_A") (pintype "passive"))
      (node (ref "IC2") (pin "24") (pinfunction "C1_24") (pintype "bidirectional"))
      (node (ref "RCM1") (pin "2") (pinfunction "2_2") (pintype "passive"))
    )
    (net (code "17") (name "C2") (class "Default")
      (node (ref "QB2") (pin "2") (pinfunction "S_2") (pintype "passive"))
      (node (ref "RCM2") (pin "1") (pinfunction "1_1") (pintype "passive"))
      (node (ref "RP3") (pin "1") (pinfunction "1_1") (pintype "passive"))
      (node (ref "X1") (pin "6") (pinfunction "6_6") (pintype "bidirectional"))
    )
    (net (code "18") (name "C2M") (class "Default")
      (node (ref "CCM2") (pin "1") (pinfunction "1_1") (pintype "passive"))
      (node (ref "CCM3") (pin "2") (pinfunction "2_2") (pintype "passive"))
      (node (ref "DCM2") (pin "C") (pinfunction "C_C") (pintype "passive"))
      (node (ref "DCM3") (pin "A") (pinfunction "A_A") (pintype "passive"))
      (node (ref "IC2") (pin "22") (pinfunction "C2_22") (pintype "bidirectional"))
      (node (ref "RCM2") (pin "2") (pinfunction "2_2") (pintype "passive"))
    )
    (net (code "19") (name "C3") (class "Default")
      (node (ref "QB3") (pin "2") (pinfunction "S_2") (pintype "passive"))
      (node (ref "RCM3") (pin "1") (pinfunction "1_1") (pintype "passive"))
      (node (ref "RP4") (pin "1") (pinfunction "1_1") (pintype "passive"))
      (node (ref "X2") (pin "2") (pinfunction "2_2") (pintype "bidirectional"))
    )
    (net (code "20") (name "C3M") (class "Default")
      (node (ref "CCM3") (pin "1") (pinfunction "1_1") (pintype "passive"))
      (node (ref "CCM4") (pin "2") (pinfunction "2_2") (pintype "passive"))
      (node (ref "DCM3") (pin "C") (pinfunction "C_C") (pintype "passive"))
      (node (ref "DCM4") (pin "A") (pinfunction "A_A") (pintype "passive"))
      (node (ref "IC2") (pin "20") (pinfunction "C3_20") (pintype "bidirectional"))
      (node (ref "RCM3") (pin "2") (pinfunction "2_2") (pintype "passive"))
    )
    (net (code "21") (name "C4") (class "Default")
      (node (ref "QB4") (pin "2") (pinfunction "S_2") (pintype "passive"))
      (node (ref "RCM4") (pin "1") (pinfunction "1_1") (pintype "passive"))
      (node (ref "RP5") (pin "1") (pinfunction "1_1") (pintype "passive"))
      (node (ref "X1") (pin "5") (pinfunction "5_5") (pintype "bidirectional"))
    )
    (net (code "22") (name "C4M") (class "Default")
      (node (ref "CCM4") (pin "1") (pinfunction "1_1") (pintype "passive"))
      (node (ref "CCM5") (pin "2") (pinfunction "2_2") (pintype "passive"))
      (node (ref "DCM4") (pin "C") (pinfunction "C_C") (pintype "passive"))
      (node (ref "DCM5") (pin "A") (pinfunction "A_A") (pintype "passive"))
      (node (ref "IC2") (pin "18") (pinfunction "C4_18") (pintype "bidirectional"))
      (node (ref "RCM4") (pin "2") (pinfunction "2_2") (pintype "passive"))
    )
    (net (code "23") (name "C5") (class "Default")
      (node (ref "QB5") (pin "2") (pinfunction "S_2") (pintype "passive"))
      (node (ref "RCM5") (pin "1") (pinfunction "1_1") (pintype "passive"))
      (node (ref "RP6") (pin "1") (pinfunction "1_1") (pintype "passive"))
      (node (ref "X2") (pin "3") (pinfunction "3_3") (pintype "bidirectional"))
    )
    (net (code "24") (name "C5M") (class "Default")
      (node (ref "CCM5") (pin "1") (pinfunction "1_1") (pintype "passive"))
      (node (ref "CCM6") (pin "2") (pinfunction "2_2") (pintype "passive"))
      (node (ref "DCM5") (pin "C") (pinfunction "C_C") (pintype "passive"))
      (node (ref "DCM6") (pin "A") (pinfunction "A_A") (pintype "passive"))
      (node (ref "IC2") (pin "16") (pinfunction "C5_16") (pintype "bidirectional"))
      (node (ref "RCM5") (pin "2") (pinfunction "2_2") (pintype "passive"))
    )
    (net (code "25") (name "C6") (class "Default")
      (node (ref "QB6") (pin "2") (pinfunction "S_2") (pintype "passive"))
      (node (ref "RCM6") (pin "1") (pinfunction "1_1") (pintype "passive"))
      (node (ref "RP7") (pin "1") (pinfunction "1_1") (pintype "passive"))
      (node (ref "X1") (pin "4") (pinfunction "4_4") (pintype "bidirectional"))
    )
    (net (code "26") (name "C6M") (class "Default")
      (node (ref "CCM6") (pin "1") (pinfunction "1_1") (pintype "passive"))
      (node (ref "CCM7") (pin "2") (pinfunction "2_2") (pintype "passive"))
      (node (ref "DCM6") (pin "C") (pinfunction "C_C") (pintype "passive"))
      (node (ref "DCM7") (pin "A") (pinfunction "A_A") (pintype "passive"))
      (node (ref "IC2") (pin "14") (pinfunction "C6_14") (pintype "bidirectional"))
      (node (ref "RCM6") (pin "2") (pinfunction "2_2") (pintype "passive"))
    )
    (net (code "27") (name "C7") (class "Default")
      (node (ref "QB7") (pin "2") (pinfunction "S_2") (pintype "passive"))
      (node (ref "RCM7") (pin "1") (pinfunction "1_1") (pintype "passive"))
      (node (ref "RP8") (pin "1") (pinfunction "1_1") (pintype "passive"))
      (node (ref "X2") (pin "4") (pinfunction "4_4") (pintype "bidirectional"))
    )
    (net (code "28") (name "C7M") (class "Default")
      (node (ref "CCM7") (pin "1") (pinfunction "1_1") (pintype "passive"))
      (node (ref "CCM8") (pin "2") (pinfunction "2_2") (pintype "passive"))
      (node (ref "DCM7") (pin "C") (pinfunction "C_C") (pintype "passive"))
      (node (ref "DCM8") (pin "A") (pinfunction "A_A") (pintype "passive"))
      (node (ref "IC2") (pin "12") (pinfunction "C7_12") (pintype "bidirectional"))
      (node (ref "RCM7") (pin "2") (pinfunction "2_2") (pintype "passive"))
    )
    (net (code "29") (name "C8") (class "Default")
      (node (ref "QB8") (pin "2") (pinfunction "S_2") (pintype "passive"))
      (node (ref "RCM8") (pin "1") (pinfunction "1_1") (pintype "passive"))
      (node (ref "RP9") (pin "1") (pinfunction "1_1") (pintype "passive"))
      (node (ref "X1") (pin "3") (pinfunction "3_3") (pintype "bidirectional"))
    )
    (net (code "30") (name "C8M") (class "Default")
      (node (ref "CCM8") (pin "1") (pinfunction "1_1") (pintype "passive"))
      (node (ref "CCM9") (pin "2") (pinfunction "2_2") (pintype "passive"))
      (node (ref "DCM8") (pin "C") (pinfunction "C_C") (pintype "passive"))
      (node (ref "DCM9") (pin "A") (pinfunction "A_A") (pintype "passive"))
      (node (ref "IC2") (pin "10") (pinfunction "C8_10") (pintype "bidirectional"))
      (node (ref "RCM8") (pin "2") (pinfunction "2_2") (pintype "passive"))
    )
    (net (code "31") (name "C9") (class "Default")
      (node (ref "QB9") (pin "2") (pinfunction "S_2") (pintype "passive"))
      (node (ref "RCM9") (pin "1") (pinfunction "1_1") (pintype "passive"))
      (node (ref "RP10") (pin "1") (pinfunction "1_1") (pintype "passive"))
      (node (ref "X2") (pin "5") (pinfunction "5_5") (pintype "bidirectional"))
    )
    (net (code "32") (name "C9M") (class "Default")
      (node (ref "CCM10") (pin "2") (pinfunction "2_2") (pintype "passive"))
      (node (ref "CCM9") (pin "1") (pinfunction "1_1") (pintype "passive"))
      (node (ref "DCM10") (pin "A") (pinfunction "A_A") (pintype "passive"))
      (node (ref "DCM9") (pin "C") (pinfunction "C_C") (pintype "passive"))
      (node (ref "IC2") (pin "8") (pinfunction "C9_8") (pintype "bidirectional"))
      (node (ref "RCM9") (pin "2") (pinfunction "2_2") (pintype "passive"))
    )
    (net (code "33") (name "C10") (class "Default")
      (node (ref "QB10") (pin "2") (pinfunction "S_2") (pintype "passive"))
      (node (ref "RCM10") (pin "1") (pinfunction "1_1") (pintype "passive"))
      (node (ref "RP11") (pin "1") (pinfunction "1_1") (pintype "passive"))
      (node (ref "X1") (pin "2") (pinfunction "2_2") (pintype "bidirectional"))
    )
    (net (code "34") (name "C10M") (class "Default")
      (node (ref "CCM10") (pin "1") (pinfunction "1_1") (pintype "passive"))
      (node (ref "CCM11") (pin "2") (pinfunction "2_2") (pintype "passive"))
      (node (ref "DCM10") (pin "C") (pinfunction "C_C") (pintype "passive"))
      (node (ref "DCM11") (pin "A") (pinfunction "A_A") (pintype "passive"))
      (node (ref "IC2") (pin "6") (pinfunction "C10_6") (pintype "bidirectional"))
      (node (ref "RCM10") (pin "2") (pinfunction "2_2") (pintype "passive"))
    )
    (net (code "35") (name "C11") (class "Default")
      (node (ref "QB11") (pin "2") (pinfunction "S_2") (pintype "passive"))
      (node (ref "RCM11") (pin "1") (pinfunction "1_1") (pintype "passive"))
      (node (ref "RP12") (pin "1") (pinfunction "1_1") (pintype "passive"))
      (node (ref "X2") (pin "6") (pinfunction "6_6") (pintype "bidirectional"))
    )
    (net (code "36") (name "C11M") (class "Default")
      (node (ref "CCM11") (pin "1") (pinfunction "1_1") (pintype "passive"))
      (node (ref "CCM12") (pin "2") (pinfunction "2_2") (pintype "passive"))
      (node (ref "DCM11") (pin "C") (pinfunction "C_C") (pintype "passive"))
      (node (ref "DCM12") (pin "A") (pinfunction "A_A") (pintype "passive"))
      (node (ref "IC2") (pin "4") (pinfunction "C11_4") (pintype "bidirectional"))
      (node (ref "RCM11") (pin "2") (pinfunction "2_2") (pintype "passive"))
    )
    (net (code "37") (name "C12") (class "Default")
      (node (ref "L7") (pin "1") (pinfunction "1_1") (pintype "passive"))
      (node (ref "QB12") (pin "2") (pinfunction "S_2") (pintype "passive"))
      (node (ref "RCM12") (pin "1") (pinfunction "1_1") (pintype "passive"))
      (node (ref "X1") (pin "1") (pinfunction "1_1") (pintype "bidirectional"))
    )
    (net (code "38") (name "C12M") (class "Default")
      (node (ref "CCM12") (pin "1") (pinfunction "1_1") (pintype "passive"))
      (node (ref "DCM12") (pin "C") (pinfunction "C_C") (pintype "passive"))
      (node (ref "IC2") (pin "2") (pinfunction "C12_2") (pintype "bidirectional"))
      (node (ref "RCM12") (pin "2") (pinfunction "2_2") (pintype "passive"))
    )
    (net (code "39") (name "CANH") (class "Default")
      (node (ref "L12") (pin "4") (pinfunction "4_4") (pintype "passive"))
      (node (ref "RV2") (pin "1") (pinfunction "1_1") (pintype "passive"))
      (node (ref "X3") (pin "2") (pinfunction "2_2") (pintype "bidirectional"))
      (node (ref "X4") (pin "2") (pinfunction "2_2") (pintype "bidirectional"))
    )
    (net (code "40") (name "CANL") (class "Default")
      (node (ref "L12") (pin "3") (pinfunction "2_3") (pintype "passive"))
      (node (ref "RV3") (pin "1") (pinfunction "1_1") (pintype "passive"))
      (node (ref "X3") (pin "3") (pinfunction "3_3") (pintype "bidirectional"))
      (node (ref "X4") (pin "3") (pinfunction "3_3") (pintype "bidirectional"))
    )
    (net (code "41") (name "CANRX") (class "Default")
      (node (ref "IC1") (pin "19") (pinfunction "CANRX_19") (pintype "bidirectional"))
      (node (ref "IC5") (pin "P$14") (pinfunction "O1_P$14") (pintype "bidirectional"))
    )
    (net (code "42") (name "CANTX") (class "Default")
      (node (ref "IC1") (pin "20") (pinfunction "CANTX_20") (pintype "bidirectional"))
      (node (ref "IC5") (pin "P$13") (pinfunction "I2_P$13") (pintype "bidirectional"))
    )
    (net (code "43") (name "CAR+5V") (class "Default")
      (node (ref "C17") (pin "1") (pinfunction "1_1") (pintype "passive"))
      (node (ref "C6") (pin "1") (pinfunction "1_1") (pintype "passive"))
      (node (ref "C7") (pin "1") (pinfunction "1_1") (pintype "passive"))
      (node (ref "IC4") (pin "3") (pinfunction "VDD_3") (pintype "bidirectional"))
      (node (ref "IC5") (pin "P$1") (pinfunction "VDD_P$1") (pintype "bidirectional"))
      (node (ref "IC5") (pin "P$6") (pinfunction "RCSEL_P$6") (pintype "bidirectional"))
      (node (ref "IC5") (pin "P$7") (pinfunction "EN1_P$7") (pintype "bidirectional"))
      (node (ref "R1") (pin "1") (pinfunction "1_1") (pintype "passive"))
      (node (ref "REG5_C3") (pin "1") (pinfunction "1_1") (pintype "passive"))
      (node (ref "REG5_L") (pin "2") (pinfunction "2_2") (pintype "passive"))
    )
    (net (code "44") (name "CARGND") (class "Default")
      (node (ref "C17") (pin "2") (pinfunction "2_2") (pintype "passive"))
      (node (ref "C6") (pin "2") (pinfunction "2_2") (pintype "passive"))
      (node (ref "C7") (pin "2") (pinfunction "2_2") (pintype "passive"))
      (node (ref "IC4") (pin "2") (pinfunction "VSS_2") (pintype "bidirectional"))
      (node (ref "IC5") (pin "P$2") (pinfunction "GND_P$2") (pintype "bidirectional"))
      (node (ref "IC5") (pin "P$5") (pinfunction "RCIN_P$5") (pintype "bidirectional"))
      (node (ref "IC5") (pin "P$8") (pinfunction "GND_P$8") (pintype "bidirectional"))
      (node (ref "IC8") (pin "2") (pinfunction "GND_2") (pintype "bidirectional"))
      (node (ref "R3") (pin "2") (pinfunction "2_2") (pintype "passive"))
      (node (ref "R39") (pin "2") (pinfunction "2_2") (pintype "passive"))
      (node (ref "REG5_C3") (pin "2") (pinfunction "2_2") (pintype "passive"))
      (node (ref "REG5_C4") (pin "2") (pinfunction "2_2") (pintype "passive"))
      (node (ref "REG5_C6") (pin "2") (pinfunction "2_2") (pintype "passive"))
      (node (ref "REG5_D2") (pin "2") (pinfunction "A_2") (pintype "passive"))
      (node (ref "RV1") (pin "2") (pinfunction "2_2") (pintype "passive"))
      (node (ref "RV2") (pin "2") (pinfunction "2_2") (pintype "passive"))
      (node (ref "RV3") (pin "2") (pinfunction "2_2") (pintype "passive"))
      (node (ref "X3") (pin "4") (pinfunction "4_4") (pintype "bidirectional"))
      (node (ref "X4") (pin "4") (pinfunction "4_4") (pintype "bidirectional"))
    )
    (net (code "45") (name "CARVIN") (class "Default")
      (node (ref "L2") (pin "1") (pinfunction "1_1") (pintype "passive"))
      (node (ref "REG5_C4") (pin "1") (pinfunction "1_1") (pintype "passive"))
      (node (ref "RV1") (pin "1") (pinfunction "1_1") (pintype "passive"))
      (node (ref "X3") (pin "1") (pinfunction "1_1") (pintype "bidirectional"))
      (node (ref "X4") (pin "1") (pinfunction "1_1") (pintype "bidirectional"))
    )
    (net (code "46") (name "FSM") (class "Default")
      (node (ref "C2") (pin "1") (pinfunction "1_1") (pintype "passive"))
      (node (ref "C4") (pin "1") (pinfunction "1_1") (pintype "passive"))
      (node (ref "IC1") (pin "33") (pinfunction "PIO1_0/AD1/CT32B1_CAP0_33") (pintype "bidirectional"))
      (node (ref "IC2") (pin "29") (pinfunction "VTEMP1_29") (pintype "bidirectional"))
      (node (ref "R59") (pin "1") (pinfunction "1_1") (pintype "passive"))
      (node (ref "R60") (pin "2") (pinfunction "2_2") (pintype "passive"))
    )
    (net (code "47") (name "GND") (class "Default")
      (node (ref "C1") (pin "2") (pinfunction "2_2") (pintype "passive"))
      (node (ref "C14") (pin "1") (pinfunction "1_1") (pintype "passive"))
      (node (ref "C15") (pin "1") (pinfunction "1_1") (pintype "passive"))
      (node (ref "C2") (pin "2") (pinfunction "2_2") (pintype "passive"))
      (node (ref "C22") (pin "2") (pinfunction "2_2") (pintype "passive"))
      (node (ref "C23") (pin "2") (pinfunction "2_2") (pintype "passive"))
      (node (ref "C27") (pin "2") (pinfunction "2_2") (pintype "passive"))
      (node (ref "C3") (pin "2") (pinfunction "2_2") (pintype "passive"))
      (node (ref "C34") (pin "2") (pinfunction "2_2") (pintype "passive"))
      (node (ref "C4") (pin "2") (pinfunction "2_2") (pintype "passive"))
      (node (ref "C5") (pin "2") (pinfunction "2_2") (pintype "passive"))
      (node (ref "C8") (pin "2") (pinfunction "2_2") (pintype "passive"))
      (node (ref "C9") (pin "2") (pinfunction "2_2") (pintype "passive"))
      (node (ref "CVREF") (pin "1") (pinfunction "1_1") (pintype "passive"))
      (node (ref "CVREG") (pin "1") (pinfunction "1_1") (pintype "passive"))
      (node (ref "DBG1") (pin "3") (pinfunction "3_3") (pintype "passive"))
      (node (ref "DBG1") (pin "5") (pinfunction "5_5") (pintype "passive"))
      (node (ref "DT1") (pin "C") (pinfunction "C_C") (pintype "passive"))
      (node (ref "DT2") (pin "C") (pinfunction "C_C") (pintype "passive"))
      (node (ref "DT3") (pin "C") (pinfunction "C_C") (pintype "passive"))
      (node (ref "DT4") (pin "C") (pinfunction "C_C") (pintype "passive"))
      (node (ref "DT5") (pin "C") (pinfunction "C_C") (pintype "passive"))
      (node (ref "DT6") (pin "C") (pinfunction "C_C") (pintype "passive"))
      (node (ref "IC1") (pin "41") (pinfunction "VSS_41") (pintype "bidirectional"))
      (node (ref "IC1") (pin "5") (pinfunction "VSS_5") (pintype "bidirectional"))
      (node (ref "IC2") (pin "27") (pinfunction "V-_27") (pintype "bidirectional"))
      (node (ref "IC2") (pin "33") (pinfunction "TOS_33") (pintype "bidirectional"))
      (node (ref "IC2") (pin "34") (pinfunction "WDTB_34") (pintype "bidirectional"))
      (node (ref "IC2") (pin "35") (pinfunction "GPIO1_35") (pintype "bidirectional"))
      (node (ref "IC2") (pin "36") (pinfunction "GPIO2_36") (pintype "bidirectional"))
      (node (ref "IC2") (pin "37") (pinfunction "A0_37") (pintype "bidirectional"))
      (node (ref "IC2") (pin "38") (pinfunction "A1_38") (pintype "bidirectional"))
      (node (ref "IC2") (pin "39") (pinfunction "A2_39") (pintype "bidirectional"))
      (node (ref "IC2") (pin "40") (pinfunction "A3_40") (pintype "bidirectional"))
      (node (ref "IC5") (pin "P$11") (pinfunction "VSEL_P$11") (pintype "bidirectional"))
      (node (ref "IC5") (pin "P$15") (pinfunction "GNDISO_P$15") (pintype "bidirectional"))
      (node (ref "IC5") (pin "P$9") (pinfunction "GNDISO_P$9") (pintype "bidirectional"))
      (node (ref "IC6") (pin "6") (pinfunction "~{E}_6") (pintype "bidirectional"))
      (node (ref "IC6") (pin "7") (pinfunction "VSS_7") (pintype "bidirectional"))
      (node (ref "IC6") (pin "8") (pinfunction "GND_8") (pintype "bidirectional"))
      (node (ref "IC7") (pin "6") (pinfunction "~{E}_6") (pintype "bidirectional"))
      (node (ref "IC7") (pin "7") (pinfunction "VSS_7") (pintype "bidirectional"))
      (node (ref "IC7") (pin "8") (pinfunction "GND_8") (pintype "bidirectional"))
      (node (ref "NTC_C1") (pin "2") (pinfunction "2_2") (pintype "passive"))
      (node (ref "NTC_C10") (pin "2") (pinfunction "2_2") (pintype "passive"))
      (node (ref "NTC_C11") (pin "2") (pinfunction "2_2") (pintype "passive"))
      (node (ref "NTC_C12") (pin "2") (pinfunction "2_2") (pintype "passive"))
      (node (ref "NTC_C2") (pin "2") (pinfunction "2_2") (pintype "passive"))
      (node (ref "NTC_C3") (pin "2") (pinfunction "2_2") (pintype "passive"))
      (node (ref "NTC_C4") (pin "2") (pinfunction "2_2") (pintype "passive"))
      (node (ref "NTC_C5") (pin "2") (pinfunction "2_2") (pintype "passive"))
      (node (ref "NTC_C6") (pin "2") (pinfunction "2_2") (pintype "passive"))
      (node (ref "NTC_C7") (pin "2") (pinfunction "2_2") (pintype "passive"))
      (node (ref "NTC_C8") (pin "2") (pinfunction "2_2") (pintype "passive"))
      (node (ref "NTC_C9") (pin "2") (pinfunction "2_2") (pintype "passive"))
      (node (ref "Q2") (pin "2") (pinfunction "S_2") (pintype "passive"))
      (node (ref "R11") (pin "1") (pinfunction "1_1") (pintype "passive"))
      (node (ref "R60") (pin "1") (pinfunction "1_1") (pintype "passive"))
      (node (ref "RGQ1_3") (pin "1") (pinfunction "1_1") (pintype "passive"))
      (node (ref "V-R") (pin "2") (pinfunction "2_2") (pintype "passive"))
      (node (ref "X2") (pin "P1") (pinfunction "P1_P1") (pintype "bidirectional"))
      (node (ref "X5") (pin "1") (pinfunction "1_1") (pintype "bidirectional"))
      (node (ref "X5") (pin "11") (pinfunction "11_11") (pintype "bidirectional"))
      (node (ref "X5") (pin "3") (pinfunction "3_3") (pintype "bidirectional"))
      (node (ref "X5") (pin "5") (pinfunction "5_5") (pintype "bidirectional"))
      (node (ref "X5") (pin "7") (pinfunction "7_7") (pintype "bidirectional"))
      (node (ref "X5") (pin "9") (pinfunction "9_9") (pintype "bidirectional"))
      (node (ref "X5") (pin "P1") (pinfunction "P1_P1") (pintype "bidirectional"))
      (node (ref "X5") (pin "P2") (pinfunction "P2_P2") (pintype "bidirectional"))
      (node (ref "X6") (pin "1") (pinfunction "1_1") (pintype "bidirectional"))
      (node (ref "X6") (pin "11") (pinfunction "11_11") (pintype "bidirectional"))
      (node (ref "X6") (pin "3") (pinfunction "3_3") (pintype "bidirectional"))
      (node (ref "X6") (pin "5") (pinfunction "5_5") (pintype "bidirectional"))
      (node (ref "X6") (pin "7") (pinfunction "7_7") (pintype "bidirectional"))
      (node (ref "X6") (pin "9") (pinfunction "9_9") (pintype "bidirectional"))
      (node (ref "Y1") (pin "P2") (pinfunction "GND_P2") (pintype "bidirectional"))
      (node (ref "Y1") (pin "P4") (pinfunction "GND1_P4") (pintype "bidirectional"))
    )
    (net (code "48") (name "ISP_CAN") (class "Default")
      (node (ref "IC1") (pin "14") (pinfunction "PIO0_3_14") (pintype "bidirectional"))
      (node (ref "R11") (pin "2") (pinfunction "2_2") (pintype "passive"))
    )
    (net (code "49") (name "ISP_ENTER") (class "Default")
      (node (ref "IC1") (pin "4") (pinfunction "PIO0_1/CLKOUT/CT32B0_MAT2_4") (pintype "bidirectional"))
      (node (ref "R15") (pin "2") (pinfunction "2_2") (pintype "passive"))
    )
    (net (code "50") (name "LED1") (class "Default")
      (node (ref "IC1") (pin "24") (pinfunction "PIO2_9_24") (pintype "bidirectional"))
      (node (ref "R2") (pin "1") (pinfunction "1_1") (pintype "passive"))
    )
    (net (code "51") (name "LED2") (class "Default")
      (node (ref "IC1") (pin "25") (pinfunction "PIO2_10_25") (pintype "bidirectional"))
      (node (ref "R8") (pin "1") (pinfunction "1_1") (pintype "passive"))
    )
    (net (code "52") (name "MISO0") (class "Default")
      (node (ref "IC1") (pin "27") (pinfunction "PIO0_8/MISO0/CT16B0_MAT0_27") (pintype "bidirectional"))
      (node (ref "IC2") (pin "43") (pinfunction "SDO_43") (pintype "bidirectional"))
      (node (ref "R19") (pin "1") (pinfunction "1_1") (pintype "passive"))
    )
    (net (code "53") (name "MISO1") (class "Default")
      (node (ref "IC1") (pin "26") (pinfunction "PIO2_2/~{DCD}/MISO1_26") (pintype "bidirectional"))
    )
    (net (code "54") (name "MOSI0") (class "Default")
      (node (ref "IC1") (pin "28") (pinfunction "PIO0_9/MOSI0/CT16B0_MAT1_28") (pintype "bidirectional"))
      (node (ref "IC2") (pin "42") (pinfunction "SDI_42") (pintype "bidirectional"))
    )
    (net (code "55") (name "MOSI1") (class "Default")
      (node (ref "IC1") (pin "38") (pinfunction "PIO2_3/~{RI}/MOSI1_38") (pintype "bidirectional"))
    )
    (net (code "56") (name "Net-(IC1-XTALIN)") (class "Default")
      (node (ref "C15") (pin "2") (pinfunction "2_2") (pintype "passive"))
      (node (ref "IC1") (pin "6") (pinfunction "XTALIN_6") (pintype "bidirectional"))
      (node (ref "Y1") (pin "P3") (pinfunction "2_P3") (pintype "passive"))
    )
    (net (code "57") (name "Net-(IC1-XTALOUT)") (class "Default")
      (node (ref "C14") (pin "2") (pinfunction "2_2") (pintype "passive"))
      (node (ref "IC1") (pin "7") (pinfunction "XTALOUT_7") (pintype "bidirectional"))
      (node (ref "Y1") (pin "P1") (pinfunction "1_P1") (pintype "passive"))
    )
    (net (code "58") (name "Net-(IC4-CANH)") (class "Default")
      (node (ref "IC4") (pin "7") (pinfunction "CANH_7") (pintype "bidirectional"))
      (node (ref "L12") (pin "1") (pinfunction "3_1") (pintype "passive"))
    )
    (net (code "59") (name "Net-(IC4-CANL)") (class "Default")
      (node (ref "IC4") (pin "6") (pinfunction "CANL_6") (pintype "bidirectional"))
      (node (ref "L12") (pin "2") (pinfunction "1_2") (pintype "passive"))
    )
    (net (code "60") (name "Net-(IC4-RS)") (class "Default")
      (node (ref "IC4") (pin "8") (pinfunction "RS_8") (pintype "bidirectional"))
      (node (ref "R39") (pin "1") (pinfunction "1_1") (pintype "passive"))
    )
    (net (code "61") (name "Net-(IC4-RX)") (class "Default")
      (node (ref "IC4") (pin "4") (pinfunction "RX_4") (pintype "bidirectional"))
      (node (ref "R41") (pin "1") (pinfunction "1_1") (pintype "passive"))
    )
    (net (code "62") (name "Net-(IC4-TX)") (class "Default")
      (node (ref "IC4") (pin "1") (pinfunction "TX_1") (pintype "bidirectional"))
      (node (ref "R40") (pin "1") (pinfunction "1_1") (pintype "passive"))
    )
    (net (code "63") (name "Net-(IC5-I1)") (class "Default")
      (node (ref "IC5") (pin "P$3") (pinfunction "I1_P$3") (pintype "bidirectional"))
      (node (ref "R41") (pin "2") (pinfunction "2_2") (pintype "passive"))
    )
    (net (code "64") (name "Net-(IC5-O2)") (class "Default")
      (node (ref "IC5") (pin "P$4") (pinfunction "O2_P$4") (pintype "bidirectional"))
      (node (ref "R40") (pin "2") (pinfunction "2_2") (pintype "passive"))
    )
    (net (code "65") (name "Net-(IC8-CB)") (class "Default")
      (node (ref "IC8") (pin "1") (pinfunction "CB_1") (pintype "bidirectional"))
      (node (ref "REG5_C2") (pin "1") (pinfunction "1_1") (pintype "passive"))
    )
    (net (code "66") (name "Net-(IC8-FB)") (class "Default")
      (node (ref "IC8") (pin "3") (pinfunction "FB_3") (pintype "bidirectional"))
      (node (ref "R1") (pin "2") (pinfunction "2_2") (pintype "passive"))
      (node (ref "R3") (pin "1") (pinfunction "1_1") (pintype "passive"))
    )
    (net (code "67") (name "Net-(IC8-SW)") (class "Default")
      (node (ref "IC8") (pin "6") (pinfunction "SW_6") (pintype "bidirectional"))
      (node (ref "REG5_C2") (pin "2") (pinfunction "2_2") (pintype "passive"))
      (node (ref "REG5_D2") (pin "1") (pinfunction "C_1") (pintype "passive"))
      (node (ref "REG5_L") (pin "1") (pinfunction "1_1") (pintype "passive"))
    )
    (net (code "68") (name "Net-(IC8-VIN)") (class "Default")
      (node (ref "IC8") (pin "4") (pinfunction "~{SHDN}_4") (pintype "bidirectional"))
      (node (ref "IC8") (pin "5") (pinfunction "VIN_5") (pintype "bidirectional"))
      (node (ref "L2") (pin "2") (pinfunction "2_2") (pintype "passive"))
      (node (ref "REG5_C6") (pin "1") (pinfunction "1_1") (pintype "passive"))
    )
    (net (code "69") (name "Net-(L7-Pad2)") (class "Default")
      (node (ref "L7") (pin "2") (pinfunction "2_2") (pintype "passive"))
      (node (ref "V+R") (pin "1") (pinfunction "1_1") (pintype "passive"))
    )
    (net (code "70") (name "Net-(LED1-PadC)") (class "Default")
      (node (ref "LED1") (pin "C") (pinfunction "C_C") (pintype "passive"))
      (node (ref "R2") (pin "2") (pinfunction "2_2") (pintype "passive"))
    )
    (net (code "71") (name "Net-(LED2-PadC)") (class "Default")
      (node (ref "LED2") (pin "C") (pinfunction "C_C") (pintype "passive"))
      (node (ref "R8") (pin "2") (pinfunction "2_2") (pintype "passive"))
    )
    (net (code "72") (name "Net-(Q1-G)") (class "Default")
      (node (ref "D2") (pin "A") (pinfunction "A_A") (pintype "passive"))
      (node (ref "Q1") (pin "1") (pinfunction "G_1") (pintype "passive"))
      (node (ref "RGQ1_1") (pin "2") (pinfunction "2_2") (pintype "passive"))
      (node (ref "RGQ1_2") (pin "2") (pinfunction "2_2") (pintype "passive"))
    )
    (net (code "73") (name "Net-(Q1-S)") (class "Default")
      (node (ref "D1") (pin "C") (pinfunction "C_C") (pintype "passive"))
      (node (ref "D2") (pin "C") (pinfunction "C_C") (pintype "passive"))
      (node (ref "Q1") (pin "2") (pinfunction "S_2") (pintype "passive"))
      (node (ref "RGQ1_1") (pin "1") (pinfunction "1_1") (pintype "passive"))
      (node (ref "V+R") (pin "2") (pinfunction "2_2") (pintype "passive"))
    )
    (net (code "74") (name "Net-(Q2-D)") (class "Default")
      (node (ref "Q2") (pin "3") (pinfunction "D_3") (pintype "passive"))
      (node (ref "RGQ1_2") (pin "1") (pinfunction "1_1") (pintype "passive"))
    )
    (net (code "75") (name "Net-(QB1-D)") (class "Default")
      (node (ref "QB1") (pin "3") (pinfunction "D_3") (pintype "passive"))
      (node (ref "RP1") (pin "2") (pinfunction "2_2") (pintype "passive"))
    )
    (net (code "76") (name "Net-(QB1-G)") (class "Default")
      (node (ref "QB1") (pin "1") (pinfunction "G_1") (pintype "passive"))
      (node (ref "RBG1") (pin "1") (pinfunction "1_1") (pintype "passive"))
    )
    (net (code "77") (name "Net-(QB2-D)") (class "Default")
      (node (ref "QB2") (pin "3") (pinfunction "D_3") (pintype "passive"))
      (node (ref "RP2") (pin "2") (pinfunction "2_2") (pintype "passive"))
    )
    (net (code "78") (name "Net-(QB2-G)") (class "Default")
      (node (ref "QB2") (pin "1") (pinfunction "G_1") (pintype "passive"))
      (node (ref "RBG2") (pin "1") (pinfunction "1_1") (pintype "passive"))
    )
    (net (code "79") (name "Net-(QB3-D)") (class "Default")
      (node (ref "QB3") (pin "3") (pinfunction "D_3") (pintype "passive"))
      (node (ref "RP3") (pin "2") (pinfunction "2_2") (pintype "passive"))
    )
    (net (code "80") (name "Net-(QB3-G)") (class "Default")
      (node (ref "QB3") (pin "1") (pinfunction "G_1") (pintype "passive"))
      (node (ref "RBG3") (pin "1") (pinfunction "1_1") (pintype "passive"))
    )
    (net (code "81") (name "Net-(QB4-D)") (class "Default")
      (node (ref "QB4") (pin "3") (pinfunction "D_3") (pintype "passive"))
      (node (ref "RP4") (pin "2") (pinfunction "2_2") (pintype "passive"))
    )
    (net (code "82") (name "Net-(QB4-G)") (class "Default")
      (node (ref "QB4") (pin "1") (pinfunction "G_1") (pintype "passive"))
      (node (ref "RBG4") (pin "1") (pinfunction "1_1") (pintype "passive"))
    )
    (net (code "83") (name "Net-(QB5-D)") (class "Default")
      (node (ref "QB5") (pin "3") (pinfunction "D_3") (pintype "passive"))
      (node (ref "RP5") (pin "2") (pinfunction "2_2") (pintype "passive"))
    )
    (net (code "84") (name "Net-(QB5-G)") (class "Default")
      (node (ref "QB5") (pin "1") (pinfunction "G_1") (pintype "passive"))
      (node (ref "RBG5") (pin "1") (pinfunction "1_1") (pintype "passive"))
    )
    (net (code "85") (name "Net-(QB6-D)") (class "Default")
      (node (ref "QB6") (pin "3") (pinfunction "D_3") (pintype "passive"))
      (node (ref "RP6") (pin "2") (pinfunction "2_2") (pintype "passive"))
    )
    (net (code "86") (name "Net-(QB6-G)") (class "Default")
      (node (ref "QB6") (pin "1") (pinfunction "G_1") (pintype "passive"))
      (node (ref "RBG6") (pin "1") (pinfunction "1_1") (pintype "passive"))
    )
    (net (code "87") (name "Net-(QB7-D)") (class "Default")
      (node (ref "QB7") (pin "3") (pinfunction "D_3") (pintype "passive"))
      (node (ref "RP7") (pin "2") (pinfunction "2_2") (pintype "passive"))
    )
    (net (code "88") (name "Net-(QB7-G)") (class "Default")
      (node (ref "QB7") (pin "1") (pinfunction "G_1") (pintype "passive"))
      (node (ref "RBG7") (pin "1") (pinfunction "1_1") (pintype "passive"))
    )
    (net (code "89") (name "Net-(QB8-D)") (class "Default")
      (node (ref "QB8") (pin "3") (pinfunction "D_3") (pintype "passive"))
      (node (ref "RP8") (pin "2") (pinfunction "2_2") (pintype "passive"))
    )
    (net (code "90") (name "Net-(QB8-G)") (class "Default")
      (node (ref "QB8") (pin "1") (pinfunction "G_1") (pintype "passive"))
      (node (ref "RBG8") (pin "1") (pinfunction "1_1") (pintype "passive"))
    )
    (net (code "91") (name "Net-(QB9-D)") (class "Default")
      (node (ref "QB9") (pin "3") (pinfunction "D_3") (pintype "passive"))
      (node (ref "RP9") (pin "2") (pinfunction "2_2") (pintype "passive"))
    )
    (net (code "92") (name "Net-(QB9-G)") (class "Default")
      (node (ref "QB9") (pin "1") (pinfunction "G_1") (pintype "passive"))
      (node (ref "RBG9") (pin "1") (pinfunction "1_1") (pintype "passive"))
    )
    (net (code "93") (name "Net-(QB10-D)") (class "Default")
      (node (ref "QB10") (pin "3") (pinfunction "D_3") (pintype "passive"))
      (node (ref "RP10") (pin "2") (pinfunction "2_2") (pintype "passive"))
    )
    (net (code "94") (name "Net-(QB10-G)") (class "Default")
      (node (ref "QB10") (pin "1") (pinfunction "G_1") (pintype "passive"))
      (node (ref "RBG10") (pin "1") (pinfunction "1_1") (pintype "passive"))
    )
    (net (code "95") (name "Net-(QB11-D)") (class "Default")
      (node (ref "QB11") (pin "3") (pinfunction "D_3") (pintype "passive"))
      (node (ref "RP11") (pin "2") (pinfunction "2_2") (pintype "passive"))
    )
    (net (code "96") (name "Net-(QB11-G)") (class "Default")
      (node (ref "QB11") (pin "1") (pinfunction "G_1") (pintype "passive"))
      (node (ref "RBG11") (pin "1") (pinfunction "1_1") (pintype "passive"))
    )
    (net (code "97") (name "Net-(QB12-D)") (class "Default")
      (node (ref "QB12") (pin "3") (pinfunction "D_3") (pintype "passive"))
      (node (ref "RP12") (pin "2") (pinfunction "2_2") (pintype "passive"))
    )
    (net (code "98") (name "Net-(QB12-G)") (class "Default")
      (node (ref "QB12") (pin "1") (pinfunction "G_1") (pintype "passive"))
      (node (ref "RBG12") (pin "1") (pinfunction "1_1") (pintype "passive"))
    )
    (net (code "99") (name "RXD") (class "Default")
      (node (ref "IC1") (pin "46") (pinfunction "PIO1_6/RXD/CT32B0_MAT0_46") (pintype "bidirectional"))
    )
    (net (code "100") (name "SCK0") (class "Default")
      (node (ref "IC1") (pin "22") (pinfunction "PIO0_6/SCK0_22") (pintype "bidirectional"))
      (node (ref "IC2") (pin "41") (pinfunction "SCKI_41") (pintype "bidirectional"))
    )
    (net (code "101") (name "SCK1") (class "Default")
      (node (ref "IC1") (pin "13") (pinfunction "PIO2_1/~{DSR}/SCK1_13") (pintype "bidirectional"))
    )
    (net (code "102") (name "SSEL0") (class "Default")
      (node (ref "IC1") (pin "10") (pinfunction "PIO0_2/SSEL/CT16B0_CAP0_10") (pintype "bidirectional"))
      (node (ref "IC2") (pin "44") (pinfunction "CSBI_44") (pintype "bidirectional"))
    )
    (net (code "103") (name "SSEL1") (class "Default")
      (node (ref "IC1") (pin "2") (pinfunction "PIO2_0/~{DTR}/SSEL1_2") (pintype "bidirectional"))
    )
    (net (code "104") (name "SWCLK") (class "Default")
      (node (ref "DBG1") (pin "4") (pinfunction "4_4") (pintype "passive"))
      (node (ref "IC1") (pin "29") (pinfunction "PIO0_10/SWCLK/SCK0/CT16B0_MAT2_29") (pintype "bidirectional"))
    )
    (net (code "105") (name "SWDIO") (class "Default")
      (node (ref "DBG1") (pin "2") (pinfunction "2_2") (pintype "passive"))
      (node (ref "IC1") (pin "39") (pinfunction "PIO1_3/SWDIO/AD4/CT32B1_MAT2_39") (pintype "bidirectional"))
    )
    (net (code "106") (name "TEMP0") (class "Default")
      (node (ref "IC6") (pin "1") (pinfunction "A1_1") (pintype "bidirectional"))
      (node (ref "NTC_C3") (pin "1") (pinfunction "1_1") (pintype "passive"))
      (node (ref "NTC_R3") (pin "1") (pinfunction "1_1") (pintype "passive"))
      (node (ref "X5") (pin "2") (pinfunction "2_2") (pintype "bidirectional"))
    )
    (net (code "107") (name "TEMP1") (class "Default")
      (node (ref "IC6") (pin "5") (pinfunction "A2_5") (pintype "bidirectional"))
      (node (ref "NTC_C2") (pin "1") (pinfunction "1_1") (pintype "passive"))
      (node (ref "NTC_R2") (pin "1") (pinfunction "1_1") (pintype "passive"))
      (node (ref "X5") (pin "4") (pinfunction "4_4") (pintype "bidirectional"))
    )
    (net (code "108") (name "TEMP2") (class "Default")
      (node (ref "IC6") (pin "2") (pinfunction "A3_2") (pintype "bidirectional"))
      (node (ref "NTC_C4") (pin "1") (pinfunction "1_1") (pintype "passive"))
      (node (ref "NTC_R4") (pin "1") (pinfunction "1_1") (pintype "passive"))
      (node (ref "X5") (pin "6") (pinfunction "6_6") (pintype "bidirectional"))
    )
    (net (code "109") (name "TEMP3") (class "Default")
      (node (ref "IC6") (pin "12") (pinfunction "B1_12") (pintype "bidirectional"))
      (node (ref "NTC_C1") (pin "1") (pinfunction "1_1") (pintype "passive"))
      (node (ref "NTC_R1") (pin "1") (pinfunction "1_1") (pintype "passive"))
      (node (ref "X5") (pin "8") (pinfunction "8_8") (pintype "bidirectional"))
    )
    (net (code "110") (name "TEMP4") (class "Default")
      (node (ref "IC6") (pin "14") (pinfunction "B2_14") (pintype "bidirectional"))
      (node (ref "NTC_C5") (pin "1") (pinfunction "1_1") (pintype "passive"))
      (node (ref "NTC_R5") (pin "1") (pinfunction "1_1") (pintype "passive"))
      (node (ref "X5") (pin "10") (pinfunction "10_10") (pintype "bidirectional"))
    )
    (net (code "111") (name "TEMP5") (class "Default")
      (node (ref "IC6") (pin "15") (pinfunction "B3_15") (pintype "bidirectional"))
      (node (ref "NTC_C8") (pin "1") (pinfunction "1_1") (pintype "passive"))
      (node (ref "NTC_R8") (pin "1") (pinfunction "1_1") (pintype "passive"))
      (node (ref "X5") (pin "12") (pinfunction "12_12") (pintype "bidirectional"))
    )
    (net (code "112") (name "TEMP6") (class "Default")
      (node (ref "IC7") (pin "1") (pinfunction "A1_1") (pintype "bidirectional"))
      (node (ref "NTC_C6") (pin "1") (pinfunction "1_1") (pintype "passive"))
      (node (ref "NTC_R6") (pin "1") (pinfunction "1_1") (pintype "passive"))
      (node (ref "X6") (pin "2") (pinfunction "2_2") (pintype "bidirectional"))
    )
    (net (code "113") (name "TEMP7") (class "Default")
      (node (ref "IC7") (pin "5") (pinfunction "A2_5") (pintype "bidirectional"))
      (node (ref "NTC_C7") (pin "1") (pinfunction "1_1") (pintype "passive"))
      (node (ref "NTC_R7") (pin "1") (pinfunction "1_1") (pintype "passive"))
      (node (ref "X6") (pin "4") (pinfunction "4_4") (pintype "bidirectional"))
    )
    (net (code "114") (name "TEMP8") (class "Default")
      (node (ref "IC7") (pin "2") (pinfunction "A3_2") (pintype "bidirectional"))
      (node (ref "NTC_C9") (pin "1") (pinfunction "1_1") (pintype "passive"))
      (node (ref "NTC_R9") (pin "1") (pinfunction "1_1") (pintype "passive"))
      (node (ref "X6") (pin "6") (pinfunction "6_6") (pintype "bidirectional"))
    )
    (net (code "115") (name "TEMP9") (class "Default")
      (node (ref "IC7") (pin "12") (pinfunction "B1_12") (pintype "bidirectional"))
      (node (ref "NTC_C12") (pin "1") (pinfunction "1_1") (pintype "passive"))
      (node (ref "NTC_R12") (pin "1") (pinfunction "1_1") (pintype "passive"))
      (node (ref "X6") (pin "8") (pinfunction "8_8") (pintype "bidirectional"))
    )
    (net (code "116") (name "TEMP10") (class "Default")
      (node (ref "IC7") (pin "14") (pinfunction "B2_14") (pintype "bidirectional"))
      (node (ref "NTC_C10") (pin "1") (pinfunction "1_1") (pintype "passive"))
      (node (ref "NTC_R10") (pin "1") (pinfunction "1_1") (pintype "passive"))
      (node (ref "X6") (pin "10") (pinfunction "10_10") (pintype "bidirectional"))
    )
    (net (code "117") (name "TEMP11") (class "Default")
      (node (ref "IC7") (pin "15") (pinfunction "B3_15") (pintype "bidirectional"))
      (node (ref "NTC_C11") (pin "1") (pinfunction "1_1") (pintype "passive"))
      (node (ref "NTC_R11") (pin "1") (pinfunction "1_1") (pintype "passive"))
      (node (ref "X6") (pin "12") (pinfunction "12_12") (pintype "bidirectional"))
    )
    (net (code "118") (name "TEMPR") (class "Default")
      (node (ref "C3") (pin "1") (pinfunction "1_1") (pintype "passive"))
      (node (ref "DT1") (pin "A") (pinfunction "A_A") (pintype "passive"))
      (node (ref "DT2") (pin "A") (pinfunction "A_A") (pintype "passive"))
      (node (ref "DT3") (pin "A") (pinfunction "A_A") (pintype "passive"))
      (node (ref "DT4") (pin "A") (pinfunction "A_A") (pintype "passive"))
      (node (ref "DT5") (pin "A") (pinfunction "A_A") (pintype "passive"))
      (node (ref "DT6") (pin "A") (pinfunction "A_A") (pintype "passive"))
      (node (ref "IC1") (pin "34") (pinfunction "PIO1_1/AD2/CT32B1_MAT0_34") (pintype "bidirectional"))
      (node (ref "R9") (pin "1") (pinfunction "1_1") (pintype "passive"))
    )
    (net (code "119") (name "TS0") (class "Default")
      (node (ref "IC1") (pin "18") (pinfunction "PIO2_4_18") (pintype "bidirectional"))
      (node (ref "IC6") (pin "10") (pinfunction "S0_10") (pintype "bidirectional"))
      (node (ref "IC7") (pin "10") (pinfunction "S0_10") (pintype "bidirectional"))
    )
    (net (code "120") (name "TS1") (class "Default")
      (node (ref "IC1") (pin "21") (pinfunction "PIO2_5_21") (pintype "bidirectional"))
      (node (ref "IC6") (pin "9") (pinfunction "S1_9") (pintype "bidirectional"))
      (node (ref "IC7") (pin "9") (pinfunction "S1_9") (pintype "bidirectional"))
    )
    (net (code "121") (name "TXD") (class "Default")
      (node (ref "IC1") (pin "47") (pinfunction "PIO1_7/TXD/CT32B0_MAT1_47") (pintype "bidirectional"))
    )
    (net (code "122") (name "UCT1") (class "Default")
      (node (ref "IC1") (pin "30") (pinfunction "PIO1_10/AD6/CT16B1_MAT1_30") (pintype "bidirectional"))
      (node (ref "IC6") (pin "3") (pinfunction "A_3") (pintype "bidirectional"))
    )
    (net (code "123") (name "UCT2") (class "Default")
      (node (ref "IC1") (pin "32") (pinfunction "PIO0_11/AD0/CT32B0_MAT3_32") (pintype "bidirectional"))
      (node (ref "IC6") (pin "13") (pinfunction "B_13") (pintype "bidirectional"))
    )
    (net (code "124") (name "UCT3") (class "Default")
      (node (ref "IC1") (pin "35") (pinfunction "PIO1_2/AD3/CT32B1_MAT1_35") (pintype "bidirectional"))
      (node (ref "IC7") (pin "3") (pinfunction "A_3") (pintype "bidirectional"))
    )
    (net (code "125") (name "UCT4") (class "Default")
      (node (ref "IC1") (pin "40") (pinfunction "PIO1_4/AD5/CT32B1_MAT3_40") (pintype "bidirectional"))
      (node (ref "IC7") (pin "13") (pinfunction "B_13") (pintype "bidirectional"))
    )
    (net (code "126") (name "V+") (class "Default")
      (node (ref "C1") (pin "1") (pinfunction "1_1") (pintype "passive"))
      (node (ref "IC2") (pin "1") (pinfunction "V+_1") (pintype "bidirectional"))
      (node (ref "Q1") (pin "3") (pinfunction "D_3") (pintype "passive"))
      (node (ref "R59") (pin "2") (pinfunction "2_2") (pintype "passive"))
    )
    (net (code "127") (name "VREF") (class "Default")
      (node (ref "CVREF") (pin "2") (pinfunction "2_2") (pintype "passive"))
      (node (ref "IC2") (pin "31") (pinfunction "VREF_31") (pintype "bidirectional"))
    )
    (net (code "128") (name "VREG") (class "Default")
      (node (ref "CVREG") (pin "2") (pinfunction "2_2") (pintype "passive"))
      (node (ref "IC2") (pin "32") (pinfunction "VREG_32") (pintype "bidirectional"))
    )
    (net (code "129") (name "unconnected-(DBG1-Pad6)") (class "Default")
      (node (ref "DBG1") (pin "6") (pinfunction "6_6") (pintype "passive"))
    )
    (net (code "130") (name "unconnected-(DBG1-Pad7)") (class "Default")
      (node (ref "DBG1") (pin "7") (pinfunction "7_7") (pintype "passive"))
    )
    (net (code "131") (name "unconnected-(DBG1-Pad8)") (class "Default")
      (node (ref "DBG1") (pin "8") (pinfunction "8_8") (pintype "passive"))
    )
    (net (code "132") (name "unconnected-(DBG1-Pad9)") (class "Default")
      (node (ref "DBG1") (pin "9") (pinfunction "9_9") (pintype "passive"))
    )
    (net (code "133") (name "unconnected-(IC1-PIO0_4{slash}SCL-Pad15)") (class "Default")
      (node (ref "IC1") (pin "15") (pinfunction "PIO0_4/SCL_15") (pintype "bidirectional"))
    )
    (net (code "134") (name "unconnected-(IC1-PIO0_5{slash}SDA-Pad16)") (class "Default")
      (node (ref "IC1") (pin "16") (pinfunction "PIO0_5/SDA_16") (pintype "bidirectional"))
    )
    (net (code "135") (name "unconnected-(IC1-PIO0_7{slash}~{CTS}-Pad23)") (class "Default")
      (node (ref "IC1") (pin "23") (pinfunction "PIO0_7/~{CTS}_23") (pintype "bidirectional"))
    )
    (net (code "136") (name "unconnected-(IC1-PIO1_5{slash}~{RTS}{slash}CT32B0_CAP0-Pad45)") (class "Default")
      (node (ref "IC1") (pin "45") (pinfunction "PIO1_5/~{RTS}/CT32B0_CAP0_45") (pintype "bidirectional"))
    )
    (net (code "137") (name "unconnected-(IC1-PIO1_8{slash}CT16B1_CAP0-Pad9)") (class "Default")
      (node (ref "IC1") (pin "9") (pinfunction "PIO1_8/CT16B1_CAP0_9") (pintype "bidirectional"))
    )
    (net (code "138") (name "unconnected-(IC1-PIO1_9{slash}CT16B1_MAT0-Pad17)") (class "Default")
      (node (ref "IC1") (pin "17") (pinfunction "PIO1_9/CT16B1_MAT0_17") (pintype "bidirectional"))
    )
    (net (code "139") (name "unconnected-(IC1-PIO1_11{slash}AD7-Pad42)") (class "Default")
      (node (ref "IC1") (pin "42") (pinfunction "PIO1_11/AD7_42") (pintype "bidirectional"))
    )
    (net (code "140") (name "unconnected-(IC1-PIO2_6-Pad1)") (class "Default")
      (node (ref "IC1") (pin "1") (pinfunction "PIO2_6_1") (pintype "bidirectional"))
    )
    (net (code "141") (name "unconnected-(IC1-PIO2_7-Pad11)") (class "Default")
      (node (ref "IC1") (pin "11") (pinfunction "PIO2_7_11") (pintype "bidirectional"))
    )
    (net (code "142") (name "unconnected-(IC1-PIO2_8-Pad12)") (class "Default")
      (node (ref "IC1") (pin "12") (pinfunction "PIO2_8_12") (pintype "bidirectional"))
    )
    (net (code "143") (name "unconnected-(IC1-PIO2_11{slash}SCK0-Pad31)") (class "Default")
      (node (ref "IC1") (pin "31") (pinfunction "PIO2_11/SCK0_31") (pintype "bidirectional"))
    )
    (net (code "144") (name "unconnected-(IC1-PIO3_0{slash}~{DTR}-Pad36)") (class "Default")
      (node (ref "IC1") (pin "36") (pinfunction "PIO3_0/~{DTR}_36") (pintype "bidirectional"))
    )
    (net (code "145") (name "unconnected-(IC1-PIO3_1{slash}~{DSR}-Pad37)") (class "Default")
      (node (ref "IC1") (pin "37") (pinfunction "PIO3_1/~{DSR}_37") (pintype "bidirectional"))
    )
    (net (code "146") (name "unconnected-(IC1-PIO3_2{slash}~{DCD}-Pad43)") (class "Default")
      (node (ref "IC1") (pin "43") (pinfunction "PIO3_2/~{DCD}_43") (pintype "bidirectional"))
    )
    (net (code "147") (name "unconnected-(IC1-PIO3_3{slash}~{RI}-Pad48)") (class "Default")
      (node (ref "IC1") (pin "48") (pinfunction "PIO3_3/~{RI}_48") (pintype "bidirectional"))
    )
    (net (code "148") (name "unconnected-(IC4-VRF-Pad5)") (class "Default")
      (node (ref "IC4") (pin "5") (pinfunction "VRF_5") (pintype "bidirectional"))
    )
    (net (code "149") (name "unconnected-(IC6-A4-Pad4)") (class "Default")
      (node (ref "IC6") (pin "4") (pinfunction "A4_4") (pintype "bidirectional"))
    )
    (net (code "150") (name "unconnected-(IC6-B4-Pad11)") (class "Default")
      (node (ref "IC6") (pin "11") (pinfunction "B4_11") (pintype "bidirectional"))
    )
    (net (code "151") (name "unconnected-(IC7-A4-Pad4)") (class "Default")
      (node (ref "IC7") (pin "4") (pinfunction "A4_4") (pintype "bidirectional"))
    )
    (net (code "152") (name "unconnected-(IC7-B4-Pad11)") (class "Default")
      (node (ref "IC7") (pin "11") (pinfunction "B4_11") (pintype "bidirectional"))
    )
    (net (code "153") (name "unconnected-(X1-PadP1)") (class "Default")
      (node (ref "X1") (pin "P1") (pinfunction "P1_P1") (pintype "bidirectional"))
    )
    (net (code "154") (name "unconnected-(X1-PadP2)") (class "Default")
      (node (ref "X1") (pin "P2") (pinfunction "P2_P2") (pintype "bidirectional"))
    )
    (net (code "155") (name "unconnected-(X2-PadP2)") (class "Default")
      (node (ref "X2") (pin "P2") (pinfunction "P2_P2") (pintype "bidirectional"))
    )
    (net (code "156") (name "unconnected-(X3-PadP1)") (class "Default")
      (node (ref "X3") (pin "P1") (pinfunction "P1_P1") (pintype "bidirectional"))
    )
    (net (code "157") (name "unconnected-(X3-PadP2)") (class "Default")
      (node (ref "X3") (pin "P2") (pinfunction "P2_P2") (pintype "bidirectional"))
    )
    (net (code "158") (name "unconnected-(X4-PadP1)") (class "Default")
      (node (ref "X4") (pin "P1") (pinfunction "P1_P1") (pintype "bidirectional"))
    )
    (net (code "159") (name "unconnected-(X4-PadP2)") (class "Default")
      (node (ref "X4") (pin "P2") (pinfunction "P2_P2") (pintype "bidirectional"))
    )
    (net (code "160") (name "unconnected-(X6-PadP1)") (class "Default")
      (node (ref "X6") (pin "P1") (pinfunction "P1_P1") (pintype "bidirectional"))
    )
    (net (code "161") (name "unconnected-(X6-PadP2)") (class "Default")
      (node (ref "X6") (pin "P2") (pinfunction "P2_P2") (pintype "bidirectional"))
    )
    (net (code "162") (name "~{RESET}") (class "Default")
      (node (ref "C34") (pin "1") (pinfunction "1_1") (pintype "passive"))
      (node (ref "DBG1") (pin "10") (pinfunction "10_10") (pintype "passive"))
      (node (ref "IC1") (pin "3") (pinfunction "PIO0_0/~{RESET}_3") (pintype "bidirectional"))
      (node (ref "R52") (pin "2") (pinfunction "2_2") (pintype "passive"))
    )
  )
)
